# Iridium_9603_Beacon.net
KiCad netlist of a schematic drawn in EAGLE
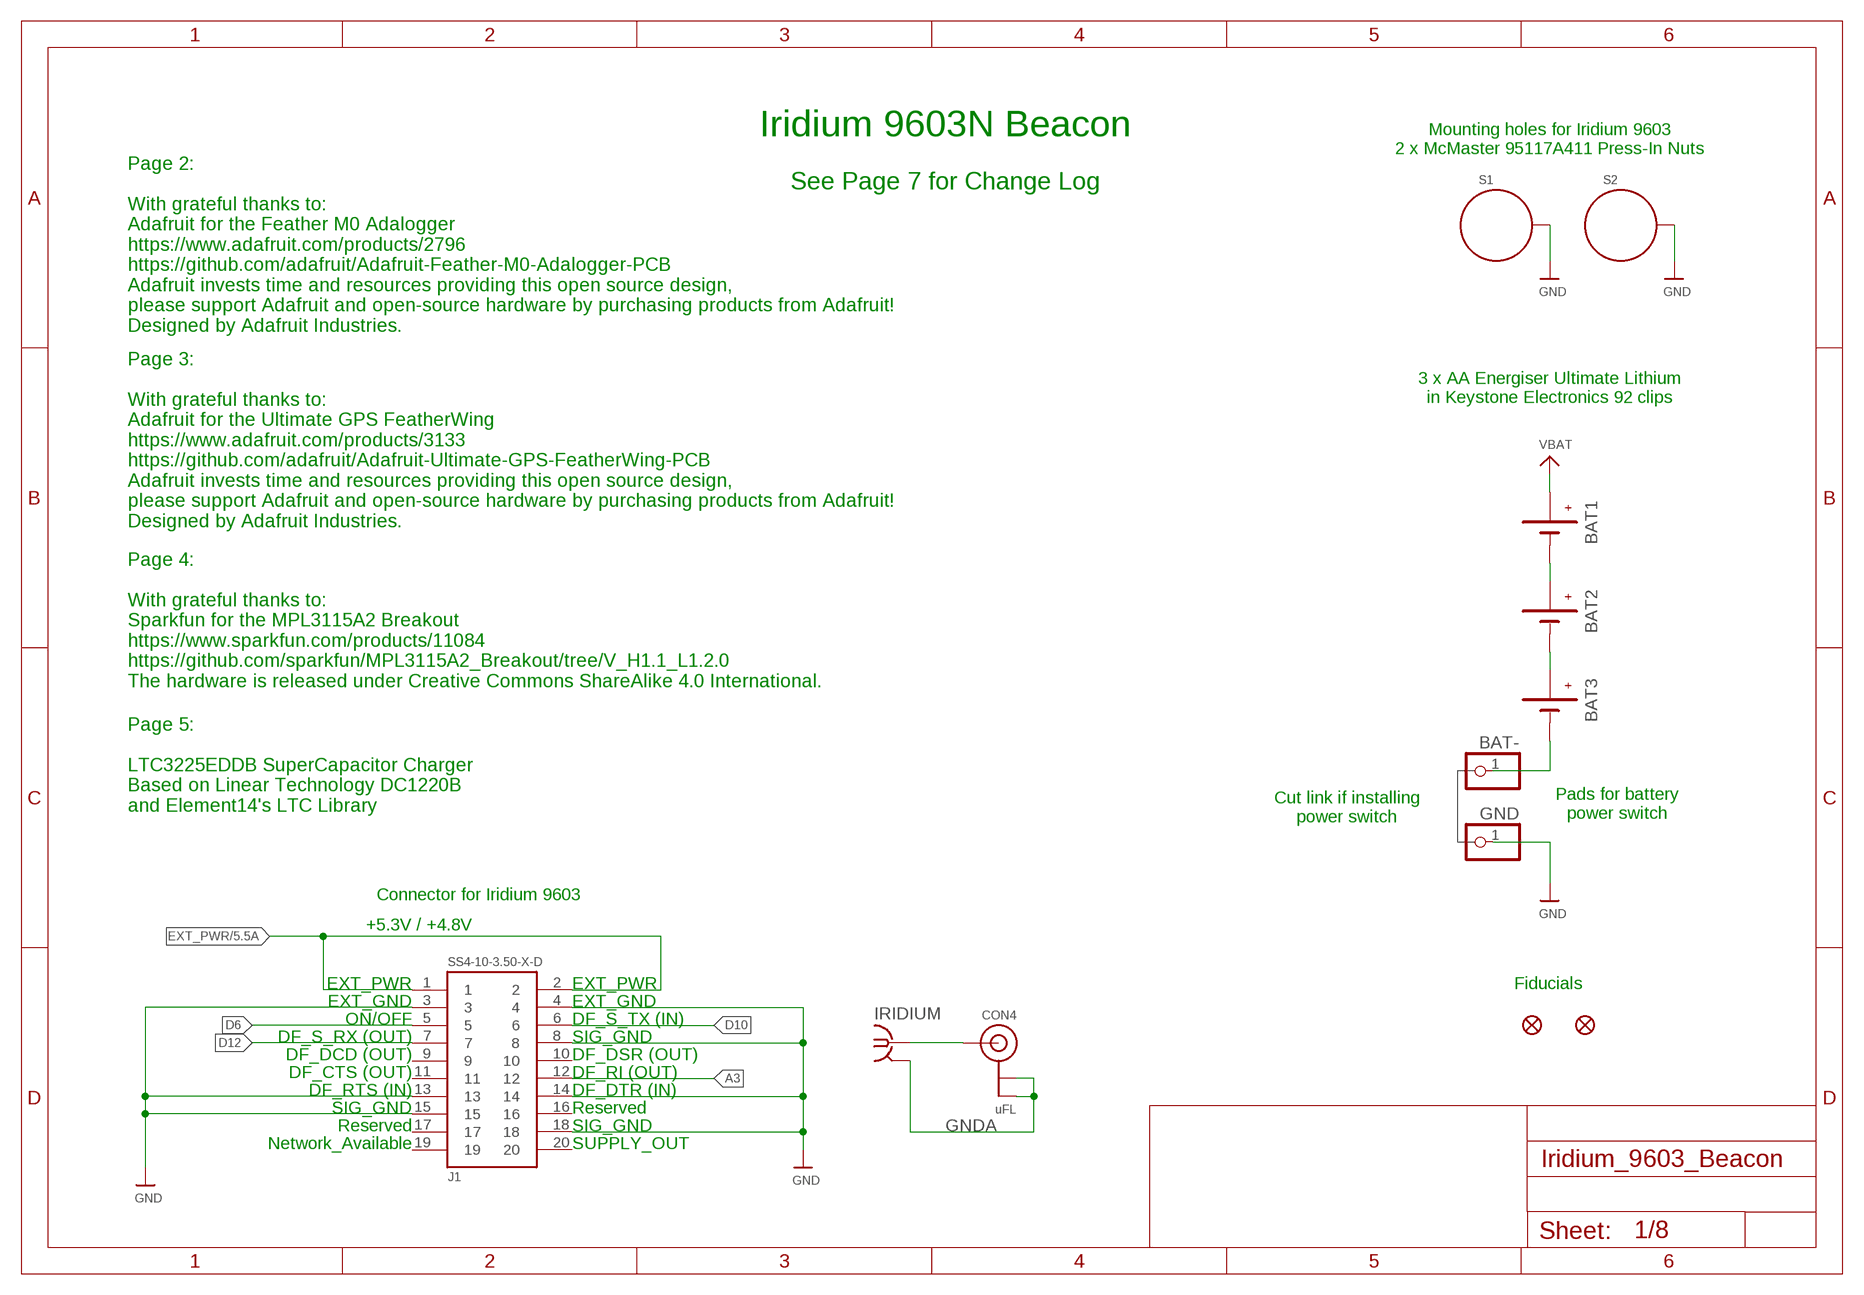
[diagram p0: schematic, sheet 1]
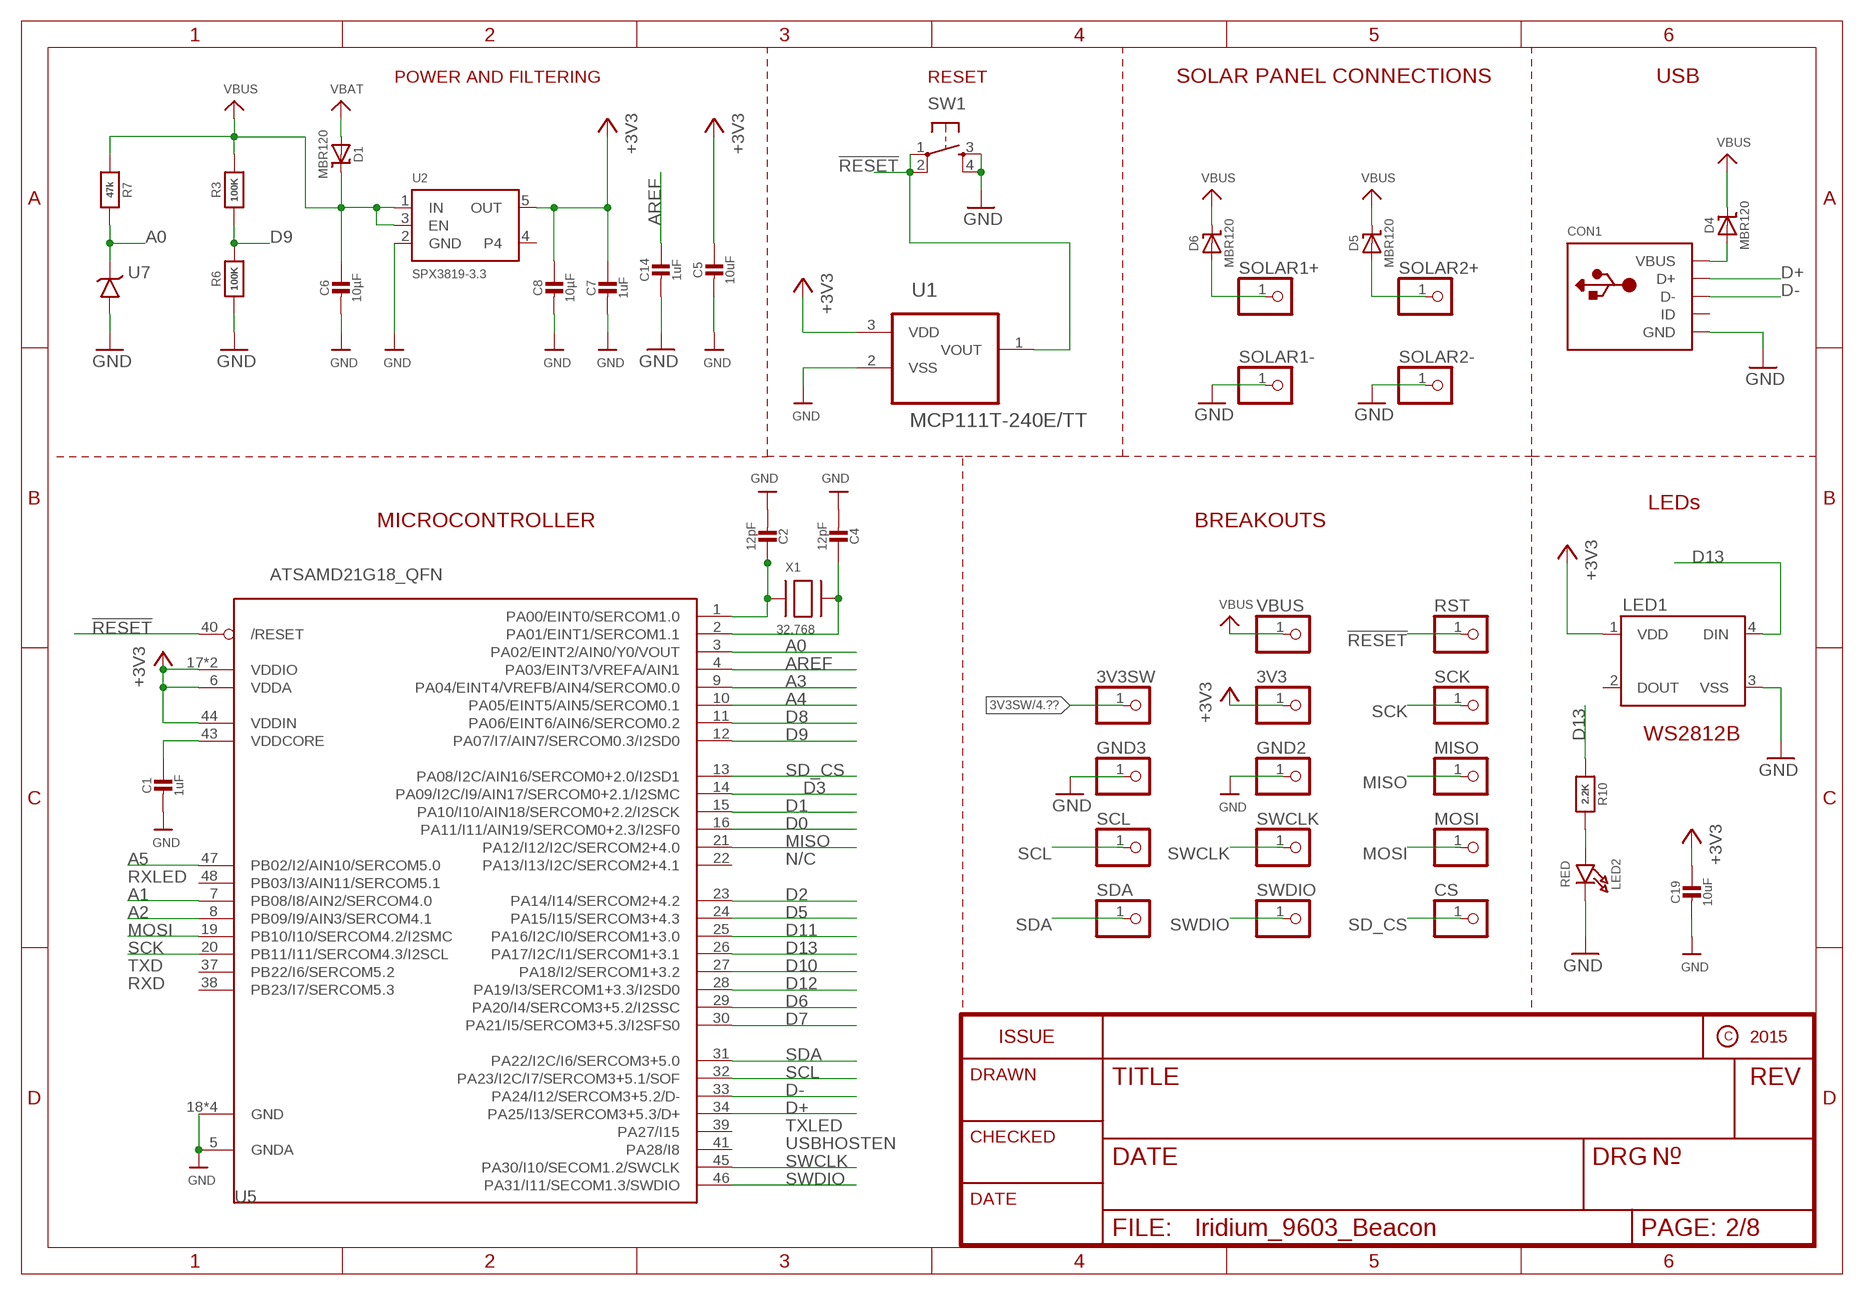
[diagram p1: schematic, sheet 2]
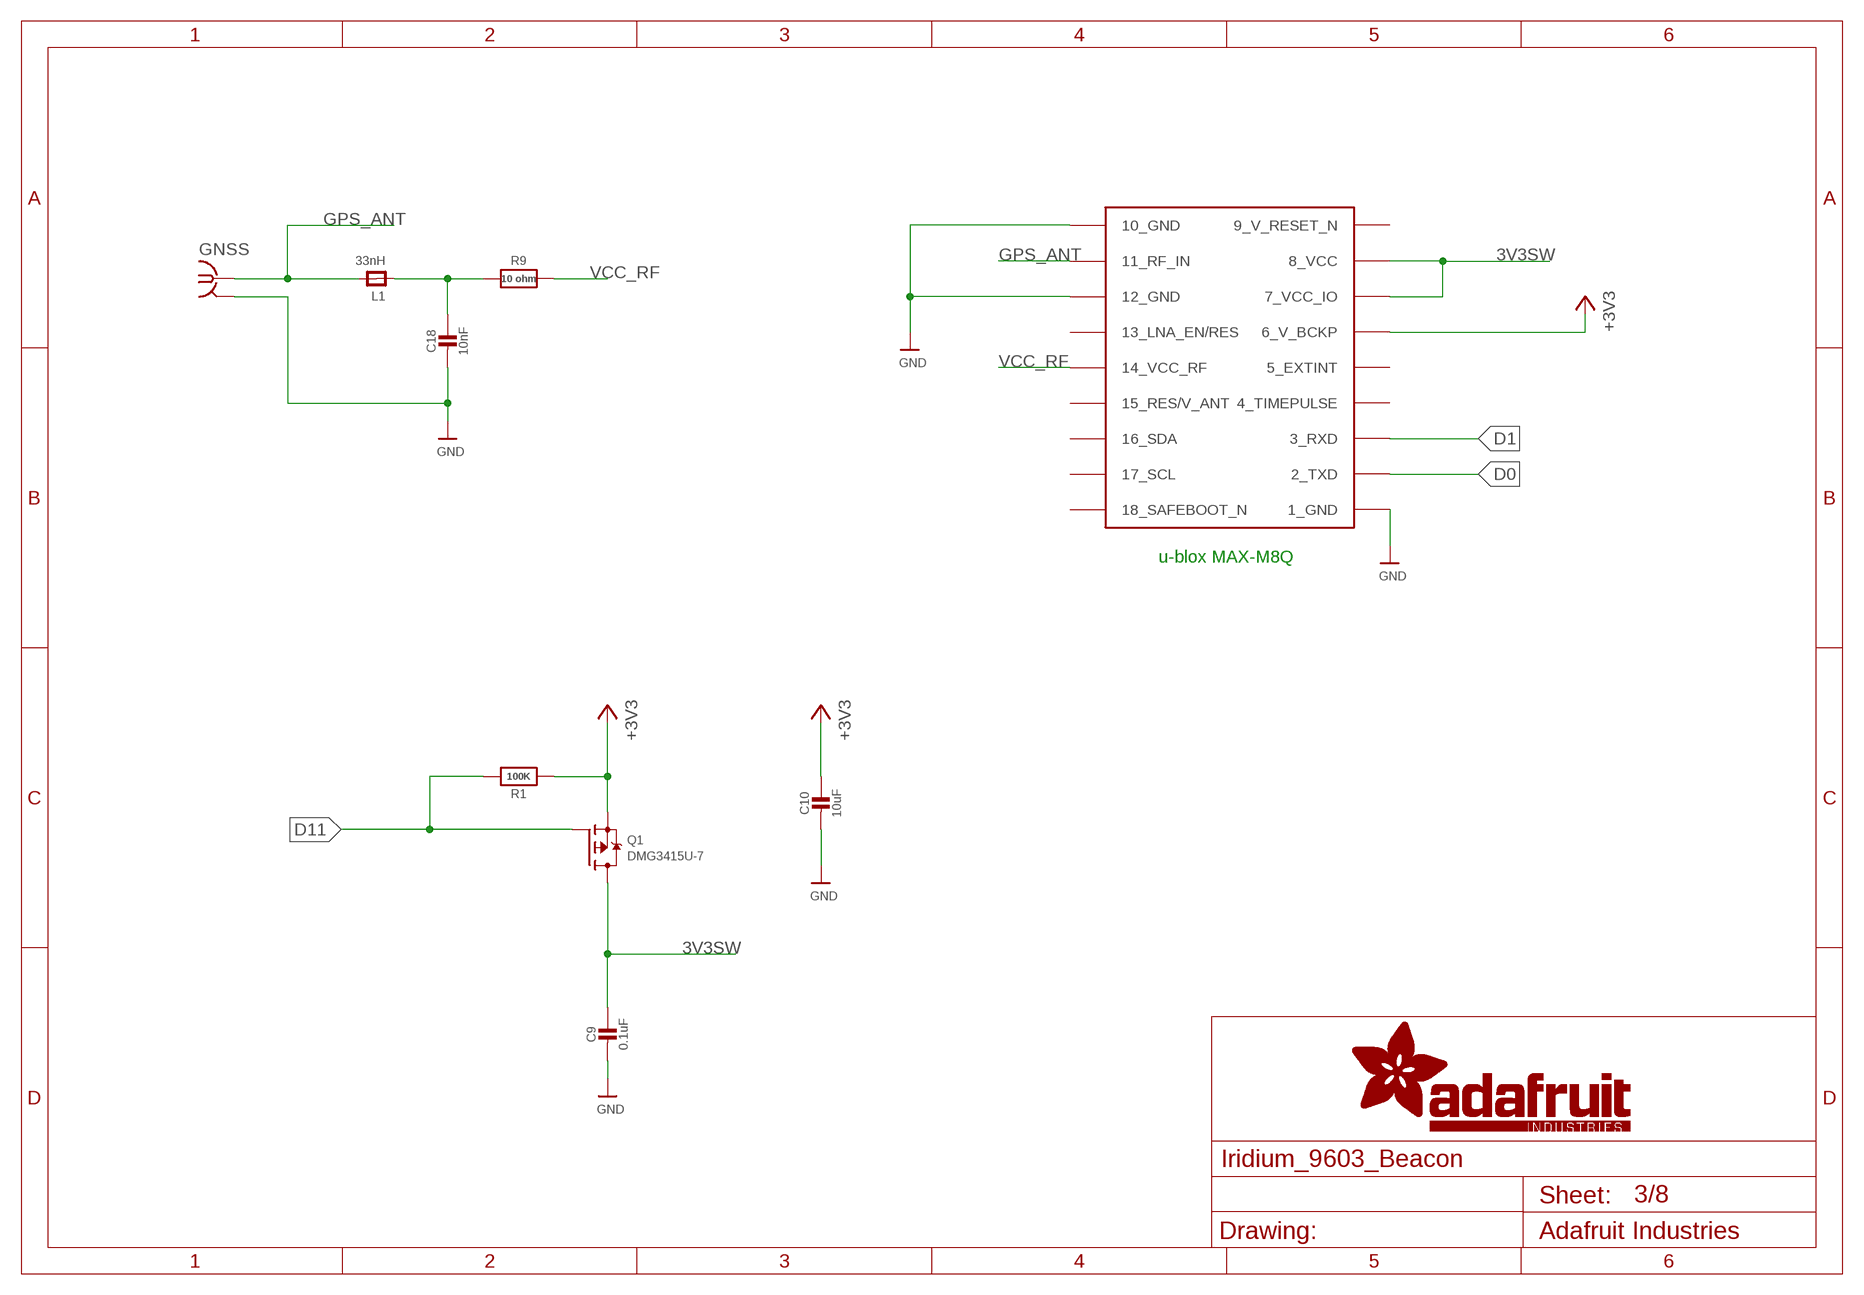
[diagram p2: schematic, sheet 3]
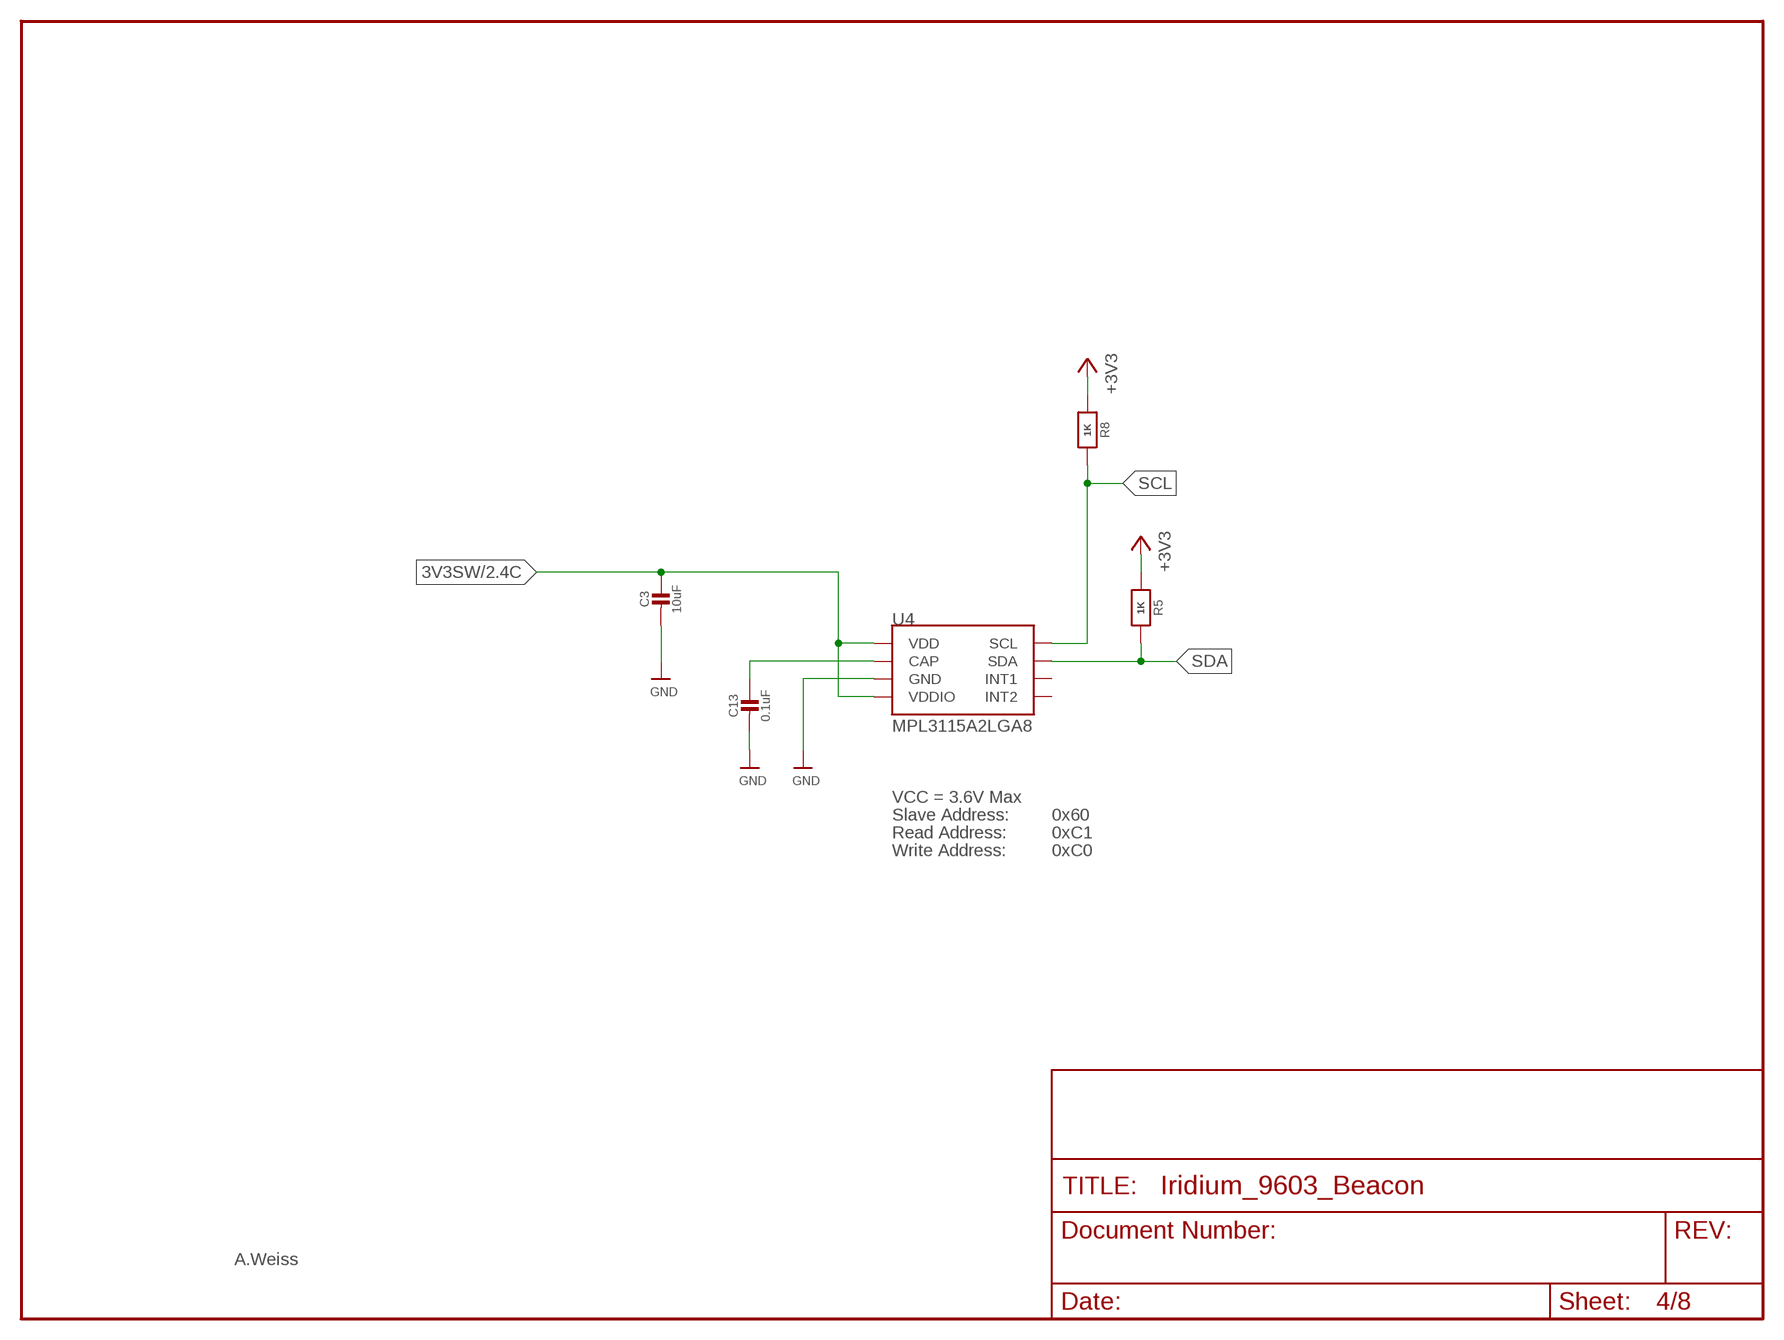
[diagram p3: schematic, sheet 4]
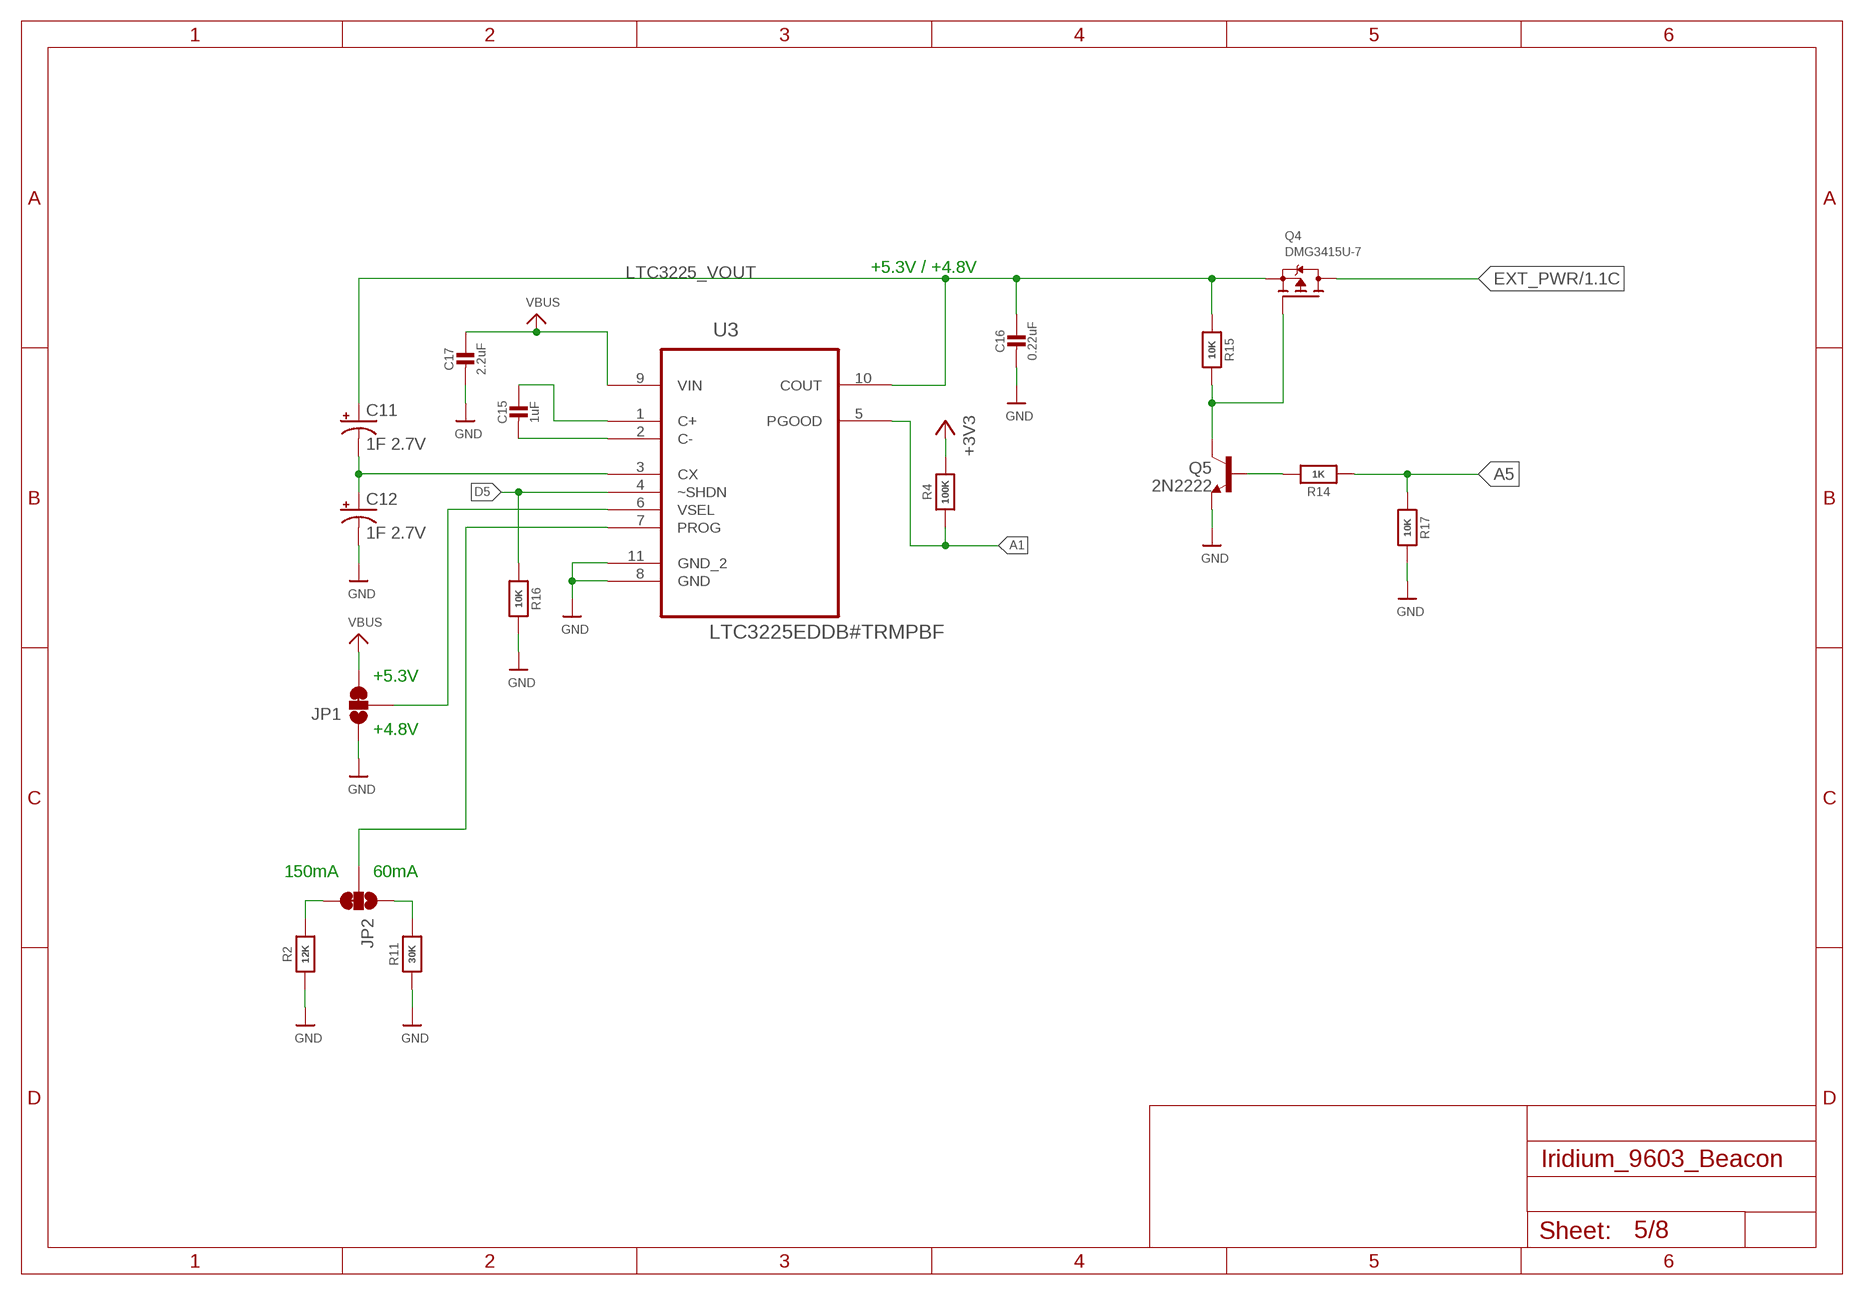
[diagram p4: schematic, sheet 5]
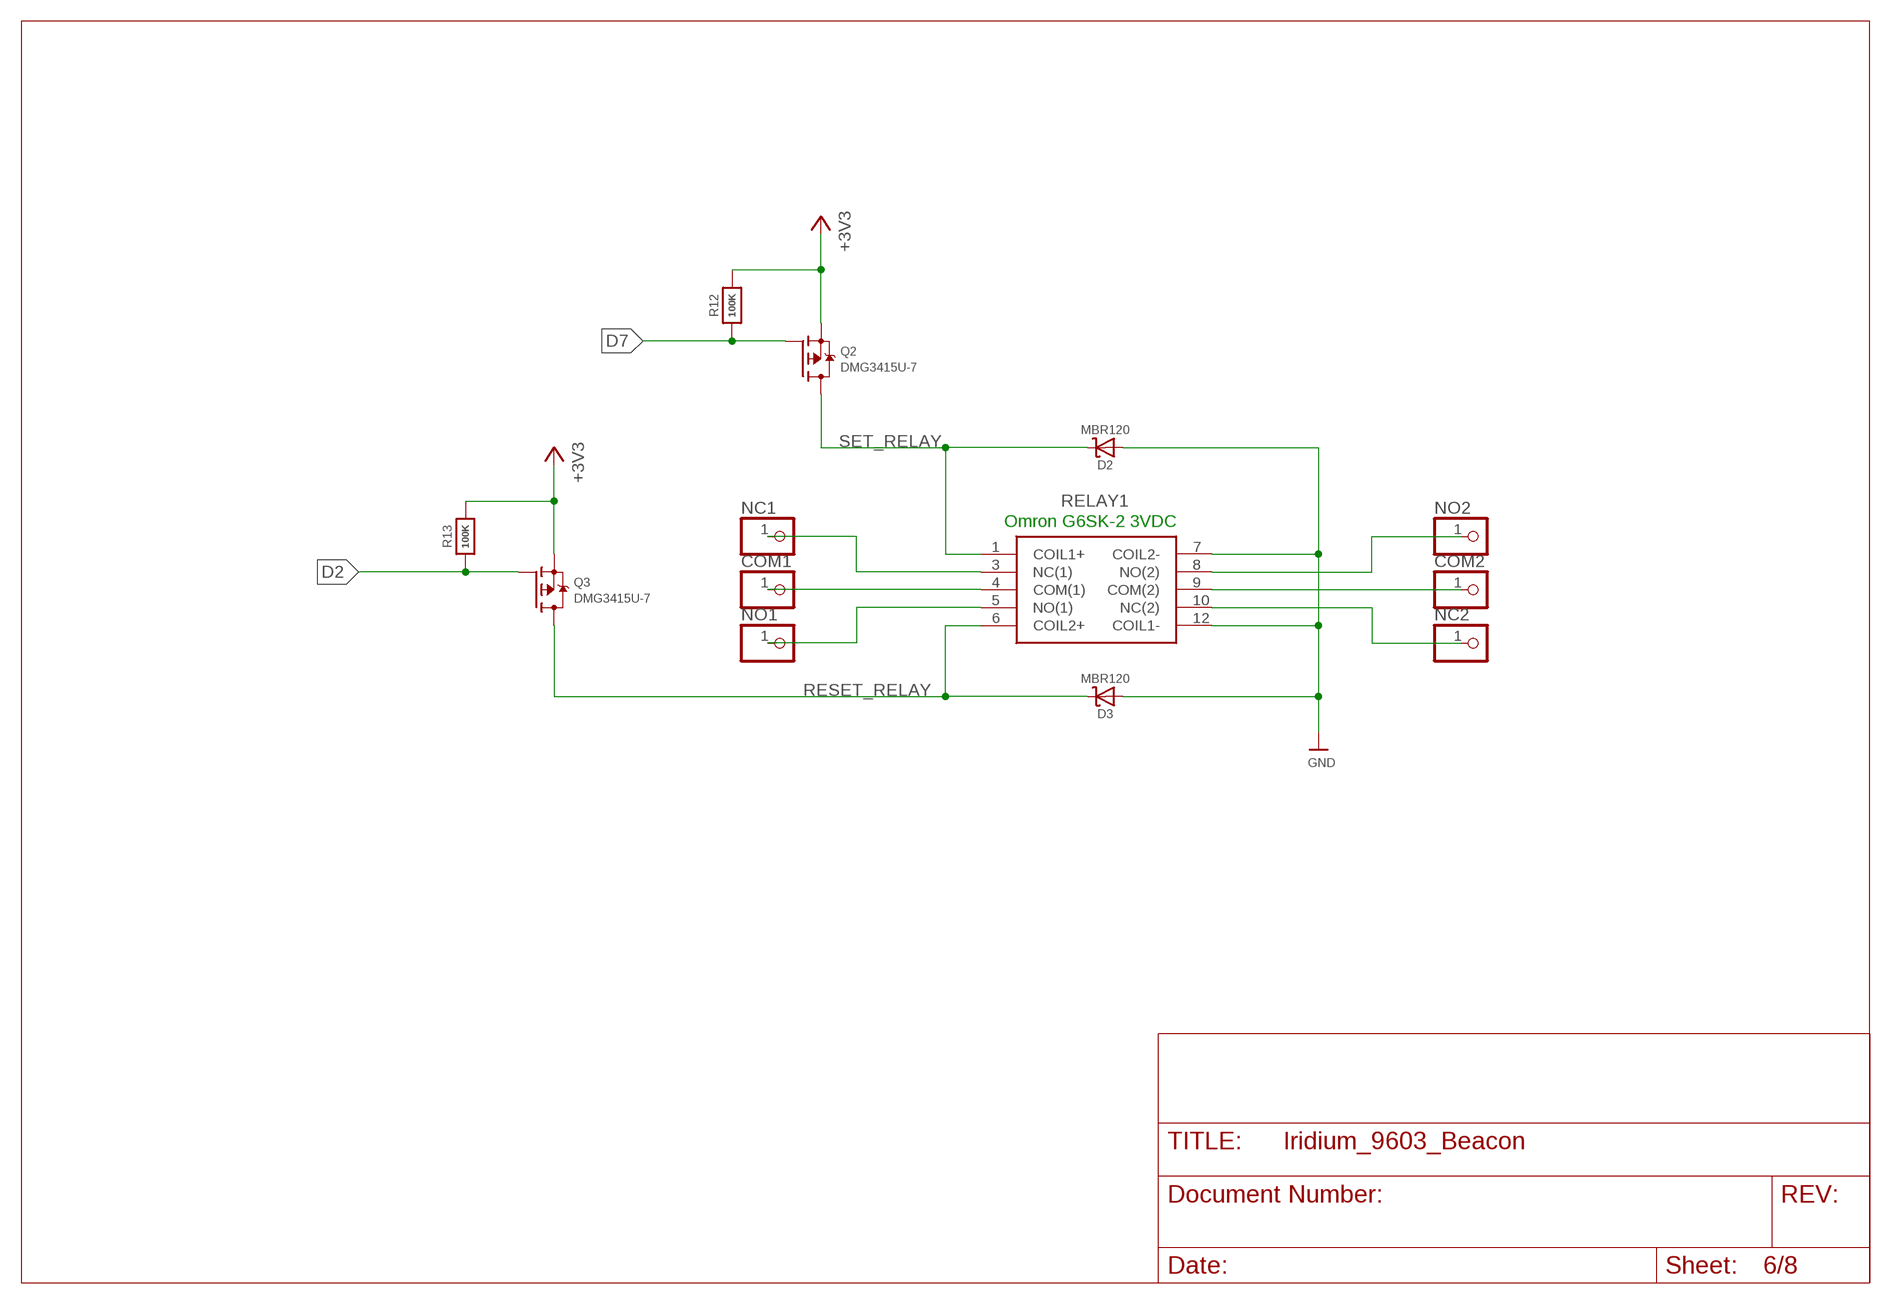
[diagram p5: schematic, sheet 6]
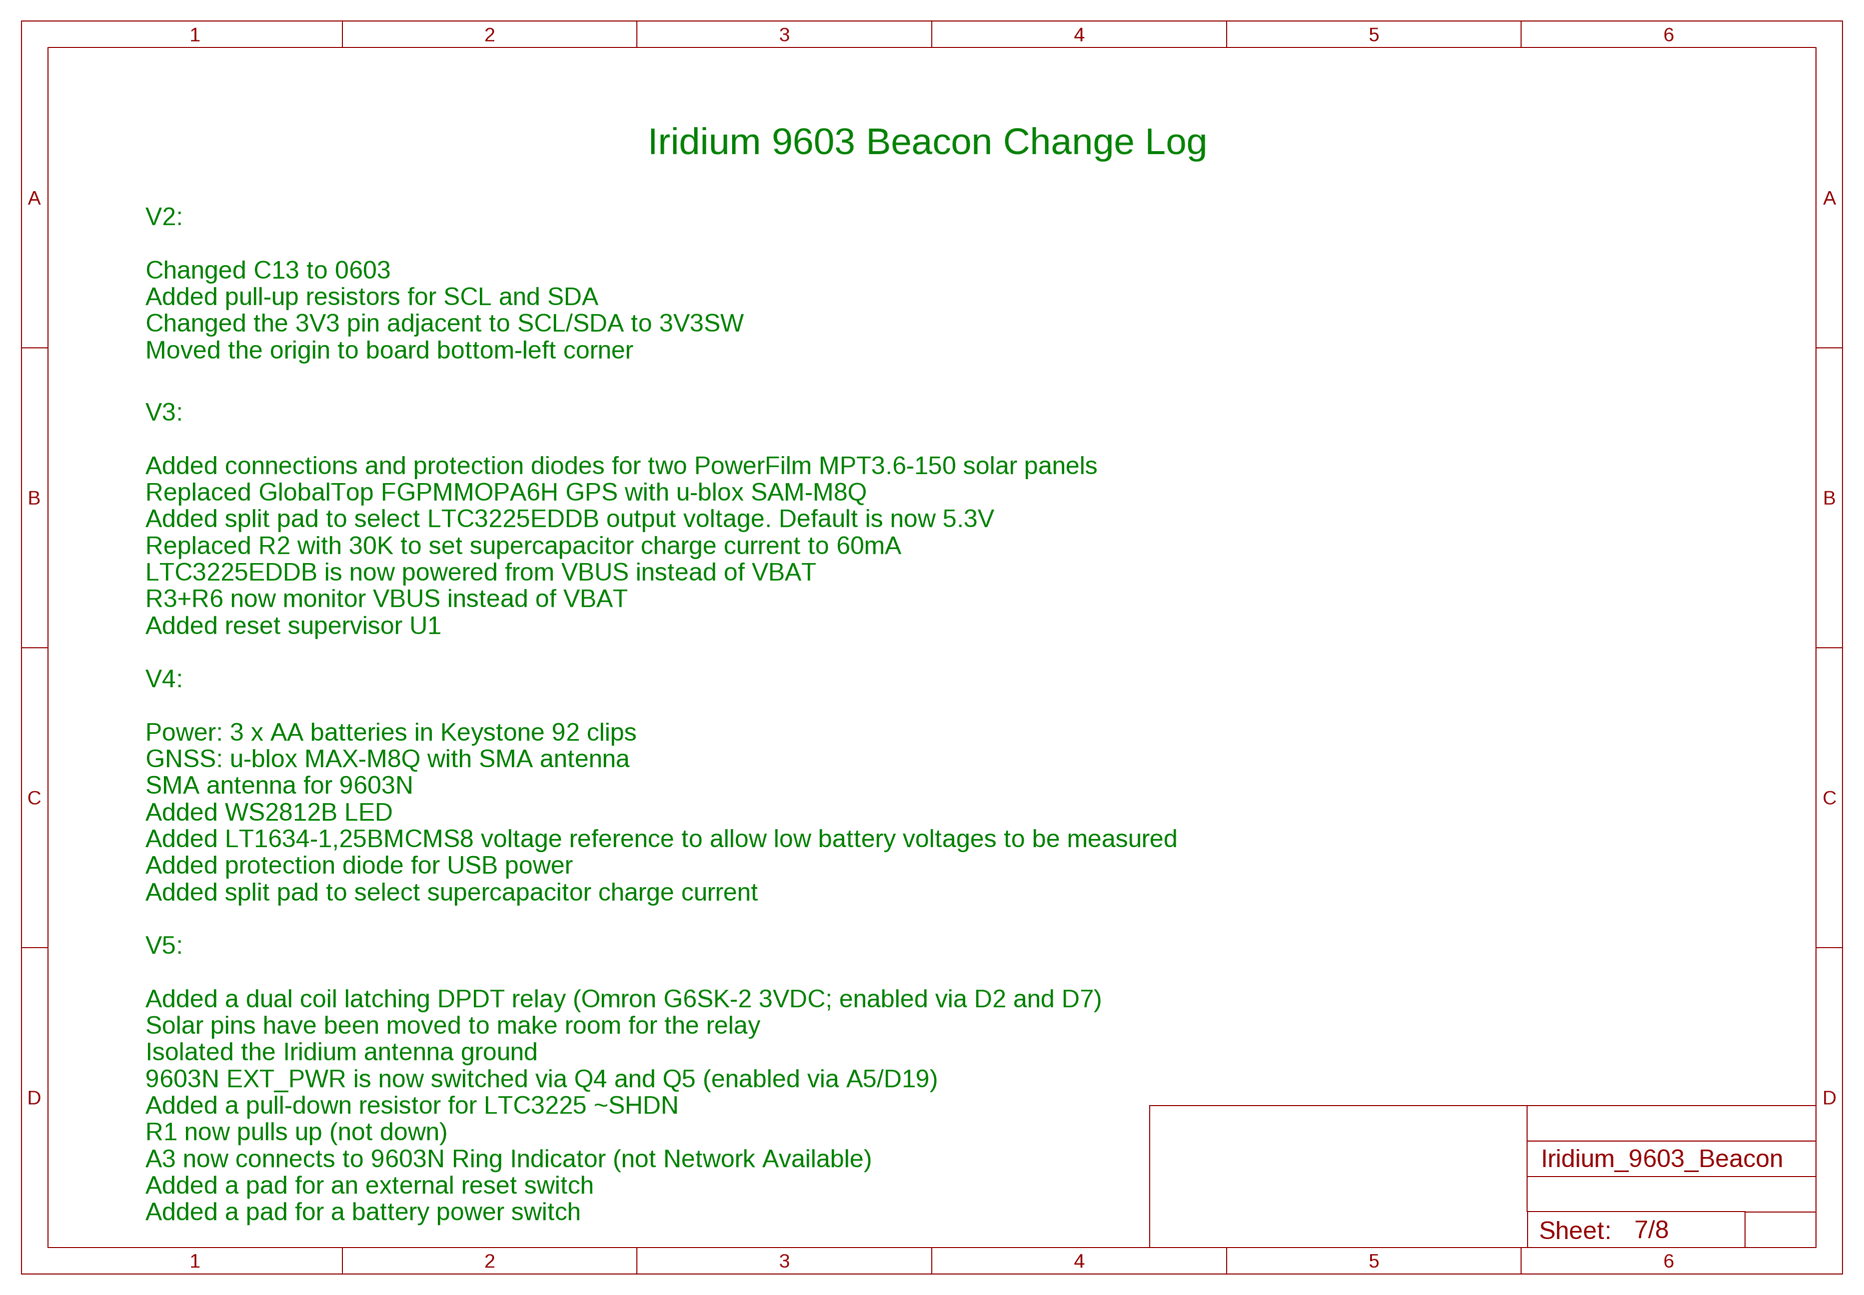
[diagram p6: schematic, sheet 7]
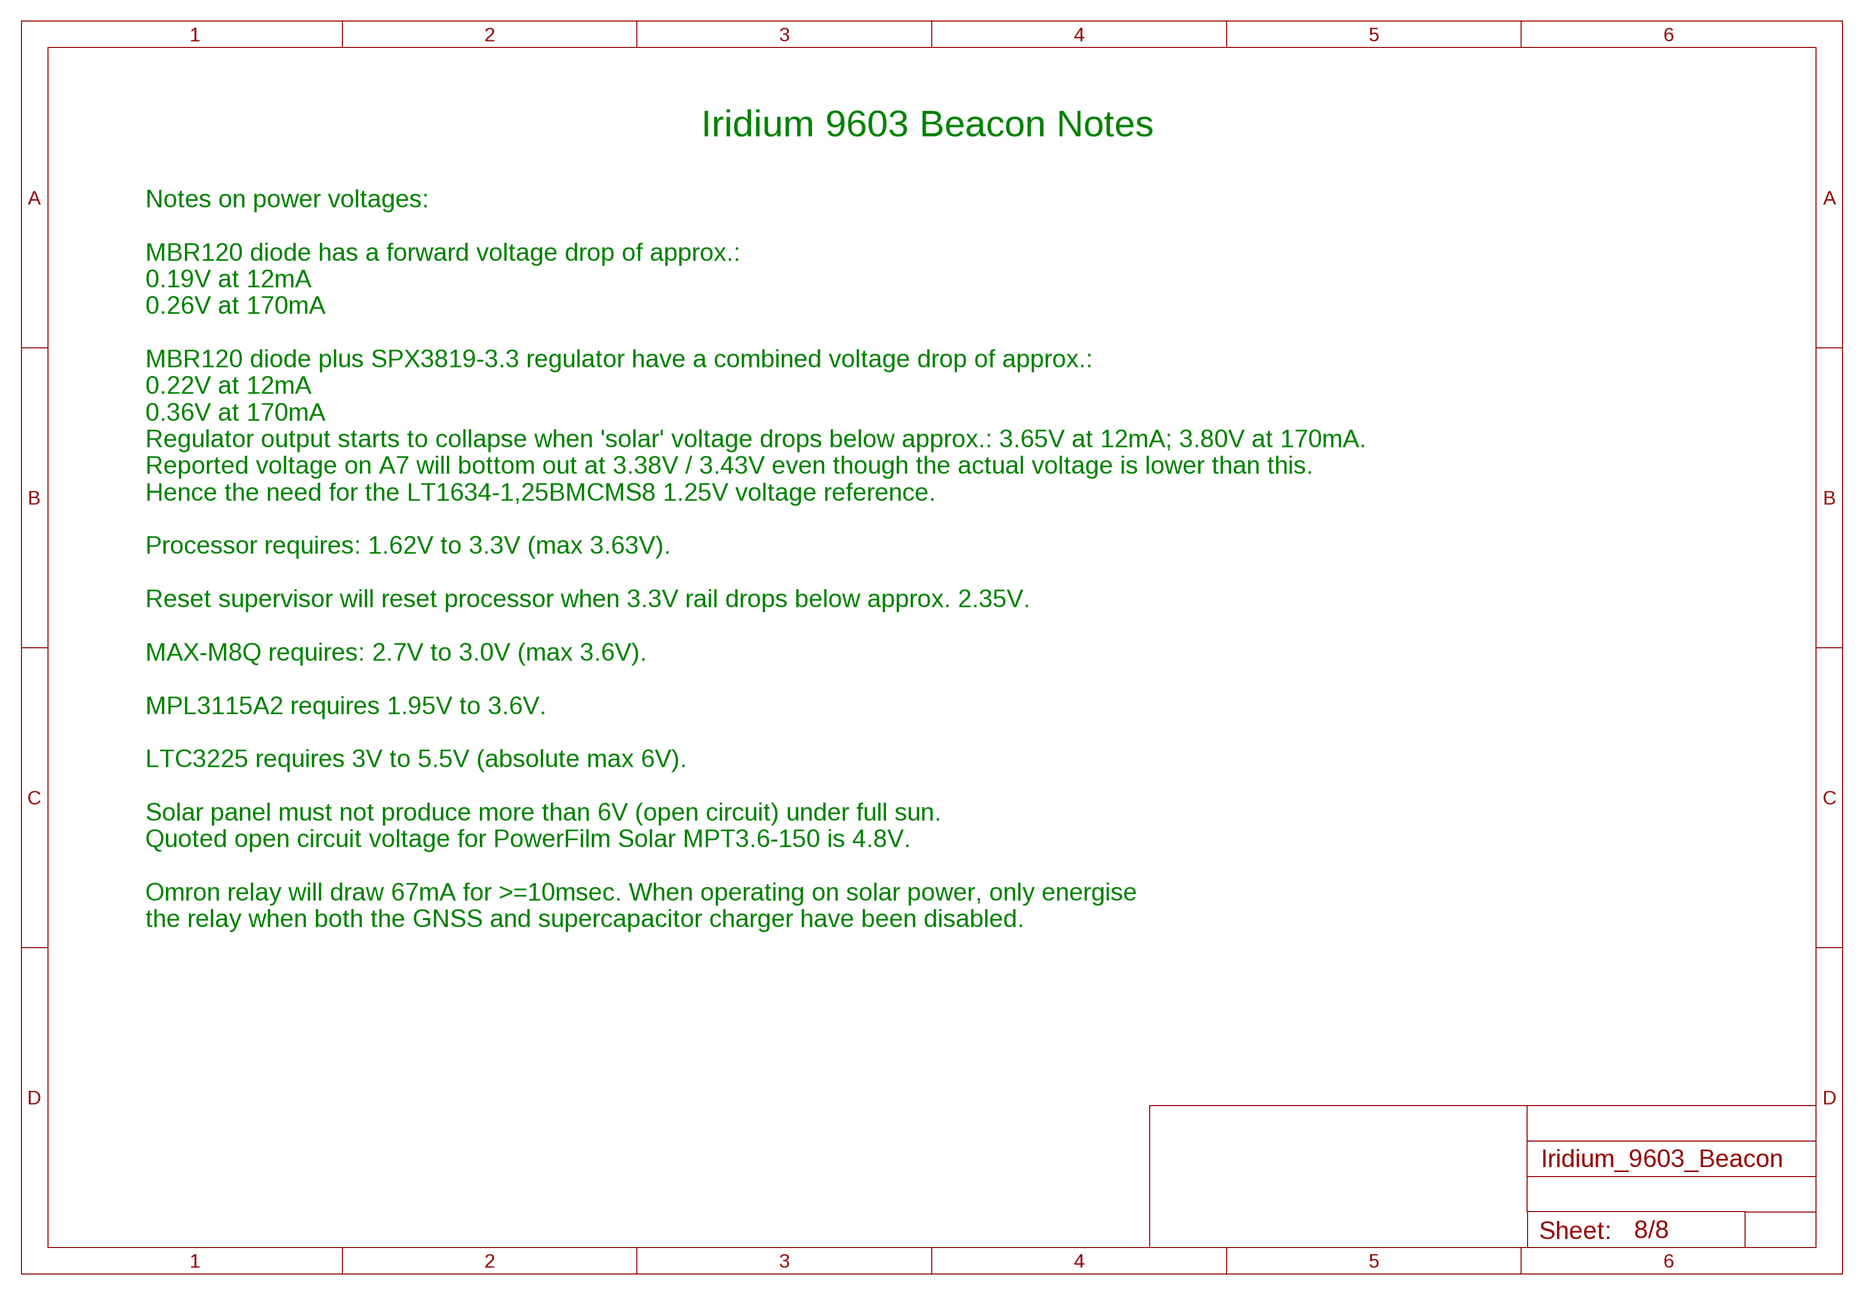
[diagram p7: schematic, sheet 8]

(export (version "E")
  (design (tool "Eeschema 10.0.6"))
  (components
    (comp (ref "C11")
      (value "1F 2.7V")
      (footprint "eagle-import:CPOL-RADIAL-1F-2.7V")
      (libsource (lib "eagle-import") (part "1F-2.7V(PTH)CPOL-RADIAL-1H-2.7V"))
    )
    (comp (ref "C12")
      (value "1F 2.7V")
      (footprint "eagle-import:CPOL-RADIAL-1F-2.7V")
      (libsource (lib "eagle-import") (part "1F-2.7V(PTH)CPOL-RADIAL-1H-2.7V"))
    )
    (comp (ref "C15")
      (value "1uF")
      (footprint "eagle-import:0603-NO")
      (libsource (lib "eagle-import") (part "CAP_CERAMIC0603_NO"))
    )
    (comp (ref "C16")
      (value "0.22uF")
      (footprint "eagle-import:0603-NO")
      (libsource (lib "eagle-import") (part "CAP_CERAMIC0603_NO"))
    )
    (comp (ref "C17")
      (value "2.2uF")
      (footprint "eagle-import:0805-NO")
      (libsource (lib "eagle-import") (part "CAP_CERAMIC0805-NOOUTLINE"))
    )
    (comp (ref "JP1")
      (value "JUMPER-PAD-3-2OF3_NC_BY_TRACE_LARGE")
      (footprint "eagle-import:PAD-JUMPER-3-2OF3_NC_BY_TRACE_YES_SILK_LARGE")
      (libsource (lib "eagle-import") (part "JUMPER-PAD-3-2OF3_NC_BY_TRACE_LARGE"))
    )
    (comp (ref "JP2")
      (value "JUMPER-PAD-3-2OF3_NC_BY_TRACE_LARGE")
      (footprint "eagle-import:PAD-JUMPER-3-2OF3_NC_BY_TRACE_YES_SILK_LARGE")
      (libsource (lib "eagle-import") (part "JUMPER-PAD-3-2OF3_NC_BY_TRACE_LARGE"))
    )
    (comp (ref "Q4")
      (value "DMG3415U-7")
      (footprint "eagle-import:SOT23-WIDE")
      (libsource (lib "eagle-import") (part "MOSFET-PWIDE"))
    )
    (comp (ref "Q5")
      (value "2N2222")
      (footprint "eagle-import:SOT23-BEC")
      (libsource (lib "eagle-import") (part "-NPN-SOT23-BECMMBT2222ALT1"))
    )
    (comp (ref "R2")
      (value "12K")
      (footprint "eagle-import:0805-NO")
      (libsource (lib "eagle-import") (part "RESISTOR0805_NOOUTLINE"))
    )
    (comp (ref "R4")
      (value "100K")
      (footprint "eagle-import:0805-NO")
      (libsource (lib "eagle-import") (part "RESISTOR0805_NOOUTLINE"))
    )
    (comp (ref "R11")
      (value "30K")
      (footprint "eagle-import:0805-NO")
      (libsource (lib "eagle-import") (part "RESISTOR0805_NOOUTLINE"))
    )
    (comp (ref "R14")
      (value "1K")
      (footprint "eagle-import:0603-NO")
      (libsource (lib "eagle-import") (part "RESISTOR_0603_NOOUT"))
    )
    (comp (ref "R15")
      (value "10K")
      (footprint "eagle-import:0603-NO")
      (libsource (lib "eagle-import") (part "RESISTOR_0603_NOOUT"))
    )
    (comp (ref "R16")
      (value "10K")
      (footprint "eagle-import:0603-NO")
      (libsource (lib "eagle-import") (part "RESISTOR_0603_NOOUT"))
    )
    (comp (ref "R17")
      (value "10K")
      (footprint "eagle-import:0603-NO")
      (libsource (lib "eagle-import") (part "RESISTOR_0603_NOOUT"))
    )
    (comp (ref "U3")
      (value "LTC3225EDDB#TRMPBF")
      (footprint "eagle-import:DFN300X200-10L")
      (libsource (lib "eagle-import") (part "LTC3225EDDB-TRMPBFDFN300X200-10L"))
    )
    (comp (ref "BAT-")
      (value "PINHD-1X1")
      (footprint "eagle-import:1X01")
      (libsource (lib "eagle-import") (part "PINHD-1X1"))
    )
    (comp (ref "BAT1")
      (value "BATTERYKEYSTONE92")
      (footprint "eagle-import:BATTERY-AAA-KEYSTONE92")
      (libsource (lib "eagle-import") (part "BATTERYKEYSTONE92"))
    )
    (comp (ref "BAT2")
      (value "BATTERYKEYSTONE92")
      (footprint "eagle-import:BATTERY-AAA-KEYSTONE92")
      (libsource (lib "eagle-import") (part "BATTERYKEYSTONE92"))
    )
    (comp (ref "BAT3")
      (value "BATTERYKEYSTONE92")
      (footprint "eagle-import:BATTERY-AAA-KEYSTONE92")
      (libsource (lib "eagle-import") (part "BATTERYKEYSTONE92"))
    )
    (comp (ref "CON4")
      (value "uFL")
      (footprint "eagle-import:U.FL")
      (libsource (lib "eagle-import") (part "ANTENNA_U.FL"))
    )
    (comp (ref "FD1")
      (value "FIDUCIAL1X2")
      (footprint "eagle-import:FIDUCIAL-1X2")
      (libsource (lib "eagle-import") (part "FIDUCIAL1X2"))
    )
    (comp (ref "FD2")
      (value "FIDUCIAL1X2")
      (footprint "eagle-import:FIDUCIAL-1X2")
      (libsource (lib "eagle-import") (part "FIDUCIAL1X2"))
    )
    (comp (ref "GND")
      (value "PINHD-1X1")
      (footprint "eagle-import:1X01")
      (libsource (lib "eagle-import") (part "PINHD-1X1"))
    )
    (comp (ref "IRIDIUM")
      (value "SMA-142-0711-821/826")
      (footprint "eagle-import:J502-ND-142-0711-821_826")
      (fields (field (name "MF") "JOHNSON COMPONENTS") (field (name "MPN") "142-0711-821"))
      (libsource (lib "eagle-import") (part "con-coax_133_SMA-142-0711-821/826"))
    )
    (comp (ref "J1")
      (value "SS4-10-3.50-X-D")
      (footprint "eagle-import:SS4-10-3.50-X-D")
      (libsource (lib "eagle-import") (part "SS4-10-3.50-X-D"))
    )
    (comp (ref "S1")
      (value "STANDOFF_ELECTRICALMCMASTER-95117A411")
      (footprint "eagle-import:STANDOFF-ELECTRICAL-MCMASTER-95117A411")
      (libsource (lib "eagle-import") (part "STANDOFF_ELECTRICALMCMASTER-95117A411"))
    )
    (comp (ref "S2")
      (value "STANDOFF_ELECTRICALMCMASTER-95117A411")
      (footprint "eagle-import:STANDOFF-ELECTRICAL-MCMASTER-95117A411")
      (libsource (lib "eagle-import") (part "STANDOFF_ELECTRICALMCMASTER-95117A411"))
    )
    (comp (ref "C3")
      (value "10uF")
      (footprint "eagle-import:0805-NO")
      (libsource (lib "eagle-import") (part "CAP_CERAMIC0805-NOOUTLINE"))
    )
    (comp (ref "C13")
      (value "0.1uF")
      (footprint "eagle-import:0805-NO")
      (libsource (lib "eagle-import") (part "CAP_CERAMIC0805-NOOUTLINE"))
    )
    (comp (ref "R5")
      (value "1K")
      (footprint "eagle-import:0603-NO")
      (libsource (lib "eagle-import") (part "RESISTOR_0603_NOOUT"))
    )
    (comp (ref "R8")
      (value "1K")
      (footprint "eagle-import:0603-NO")
      (libsource (lib "eagle-import") (part "RESISTOR_0603_NOOUT"))
    )
    (comp (ref "U4")
      (value "MPL3115A2LGA8")
      (footprint "eagle-import:LGA8")
      (libsource (lib "eagle-import") (part "MPL3115A2LGA8"))
    )
    (comp (ref "COM1")
      (value "PINHD-1X1")
      (footprint "eagle-import:1X01")
      (libsource (lib "eagle-import") (part "PINHD-1X1"))
    )
    (comp (ref "COM2")
      (value "PINHD-1X1")
      (footprint "eagle-import:1X01")
      (libsource (lib "eagle-import") (part "PINHD-1X1"))
    )
    (comp (ref "D2")
      (value "MBR120")
      (footprint "eagle-import:SOD-123")
      (libsource (lib "eagle-import") (part "DIODE-SCHOTTKYSOD-123"))
    )
    (comp (ref "D3")
      (value "MBR120")
      (footprint "eagle-import:SOD-123")
      (libsource (lib "eagle-import") (part "DIODE-SCHOTTKYSOD-123"))
    )
    (comp (ref "NC1")
      (value "PINHD-1X1")
      (footprint "eagle-import:1X01")
      (libsource (lib "eagle-import") (part "PINHD-1X1"))
    )
    (comp (ref "NC2")
      (value "PINHD-1X1")
      (footprint "eagle-import:1X01")
      (libsource (lib "eagle-import") (part "PINHD-1X1"))
    )
    (comp (ref "NO1")
      (value "PINHD-1X1")
      (footprint "eagle-import:1X01")
      (libsource (lib "eagle-import") (part "PINHD-1X1"))
    )
    (comp (ref "NO2")
      (value "PINHD-1X1")
      (footprint "eagle-import:1X01")
      (libsource (lib "eagle-import") (part "PINHD-1X1"))
    )
    (comp (ref "Q2")
      (value "DMG3415U-7")
      (footprint "eagle-import:SOT23-WIDE")
      (libsource (lib "eagle-import") (part "MOSFET-PWIDE"))
    )
    (comp (ref "Q3")
      (value "DMG3415U-7")
      (footprint "eagle-import:SOT23-WIDE")
      (libsource (lib "eagle-import") (part "MOSFET-PWIDE"))
    )
    (comp (ref "R12")
      (value "100K")
      (footprint "eagle-import:0805-NO")
      (libsource (lib "eagle-import") (part "RESISTOR0805_NOOUTLINE"))
    )
    (comp (ref "R13")
      (value "100K")
      (footprint "eagle-import:0805-NO")
      (libsource (lib "eagle-import") (part "RESISTOR0805_NOOUTLINE"))
    )
    (comp (ref "RELAY1")
      (value "G6SK-2_DC5")
      (footprint "eagle-import:G6SK2DC5")
      (fields (field (name "MANUFACTURER_PART_NUMBER") "G6SK-2 DC5"))
      (libsource (lib "eagle-import") (part "G6SK-2_DC5"))
    )
    (comp (ref "C9")
      (value "0.1uF")
      (footprint "eagle-import:0805-NO")
      (libsource (lib "eagle-import") (part "CAP_CERAMIC0805-NOOUTLINE"))
    )
    (comp (ref "C10")
      (value "10uF")
      (footprint "eagle-import:0805-NO")
      (libsource (lib "eagle-import") (part "CAP_CERAMIC0805-NOOUTLINE"))
    )
    (comp (ref "C18")
      (value "10nF")
      (footprint "eagle-import:0805-NO")
      (libsource (lib "eagle-import") (part "CAP_CERAMIC0805-NOOUTLINE"))
    )
    (comp (ref "GNSS")
      (value "SMA-142-0711-821/826")
      (footprint "eagle-import:J502-ND-142-0711-821_826")
      (fields (field (name "MF") "JOHNSON COMPONENTS") (field (name "MPN") "142-0711-821"))
      (libsource (lib "eagle-import") (part "SMA-142-0711-821/826"))
    )
    (comp (ref "L1")
      (value "33nH")
      (footprint "eagle-import:0805-NO")
      (libsource (lib "eagle-import") (part "FERRITE-0805NO"))
    )
    (comp (ref "Q1")
      (value "DMG3415U-7")
      (footprint "eagle-import:SOT23-WIDE")
      (libsource (lib "eagle-import") (part "MOSFET-PWIDE"))
    )
    (comp (ref "R1")
      (value "100K")
      (footprint "eagle-import:0805-NO")
      (libsource (lib "eagle-import") (part "RESISTOR0805_NOOUTLINE"))
    )
    (comp (ref "R9")
      (value "10 ohm")
      (footprint "eagle-import:0805-NO")
      (libsource (lib "eagle-import") (part "RESISTOR0805_NOOUTLINE"))
    )
    (comp (ref "U6")
      (value "MAX-M8")
      (footprint "eagle-import:MAX-M8")
      (libsource (lib "eagle-import") (part "MAX-M8"))
    )
    (comp (ref "3V3")
      (value "PINHD-1X1")
      (footprint "eagle-import:1X01")
      (libsource (lib "eagle-import") (part "PINHD-1X1"))
    )
    (comp (ref "3V3SW")
      (value "PINHD-1X1")
      (footprint "eagle-import:1X01")
      (libsource (lib "eagle-import") (part "PINHD-1X1"))
    )
    (comp (ref "C1")
      (value "1uF")
      (footprint "eagle-import:0603-NO")
      (libsource (lib "eagle-import") (part "CAP_CERAMIC0603_NO"))
    )
    (comp (ref "C2")
      (value "12pF")
      (footprint "eagle-import:0603-NO")
      (libsource (lib "eagle-import") (part "CAP_CERAMIC0603_NO"))
    )
    (comp (ref "C4")
      (value "12pF")
      (footprint "eagle-import:0603-NO")
      (libsource (lib "eagle-import") (part "CAP_CERAMIC0603_NO"))
    )
    (comp (ref "C5")
      (value "10uF")
      (footprint "eagle-import:0805-NO")
      (libsource (lib "eagle-import") (part "CAP_CERAMIC0805-NOOUTLINE"))
    )
    (comp (ref "C6")
      (value "10µF")
      (footprint "eagle-import:0805-NO")
      (libsource (lib "eagle-import") (part "CAP_CERAMIC0805-NOOUTLINE"))
    )
    (comp (ref "C7")
      (value "1uF")
      (footprint "eagle-import:0603-NO")
      (libsource (lib "eagle-import") (part "CAP_CERAMIC0603_NO"))
    )
    (comp (ref "C8")
      (value "10µF")
      (footprint "eagle-import:0805-NO")
      (libsource (lib "eagle-import") (part "CAP_CERAMIC0805-NOOUTLINE"))
    )
    (comp (ref "C14")
      (value "1uF")
      (footprint "eagle-import:0603-NO")
      (libsource (lib "eagle-import") (part "CAP_CERAMIC0603_NO"))
    )
    (comp (ref "C19")
      (value "10uF")
      (footprint "eagle-import:0805-NO")
      (libsource (lib "eagle-import") (part "CAP_CERAMIC0805-NOOUTLINE"))
    )
    (comp (ref "CON1")
      (value "MICROBUILDER_USBFCI_10103594_CORRECTED")
      (footprint "eagle-import:MICROBUILDER_FCI_10103594_CORRECTED")
      (libsource (lib "eagle-import") (part "MICROBUILDER_USBFCI_10103594_CORRECTED"))
    )
    (comp (ref "CS")
      (value "PINHD-1X1")
      (footprint "eagle-import:1X01")
      (libsource (lib "eagle-import") (part "PINHD-1X1"))
    )
    (comp (ref "D1")
      (value "MBR120")
      (footprint "eagle-import:SOD-123")
      (libsource (lib "eagle-import") (part "DIODE-SCHOTTKYSOD-123"))
    )
    (comp (ref "D4")
      (value "MBR120")
      (footprint "eagle-import:SOD-123")
      (libsource (lib "eagle-import") (part "DIODE-SCHOTTKYSOD-123"))
    )
    (comp (ref "D5")
      (value "MBR120")
      (footprint "eagle-import:SOD-123")
      (libsource (lib "eagle-import") (part "DIODE-SCHOTTKYSOD-123"))
    )
    (comp (ref "D6")
      (value "MBR120")
      (footprint "eagle-import:SOD-123")
      (libsource (lib "eagle-import") (part "DIODE-SCHOTTKYSOD-123"))
    )
    (comp (ref "GND2")
      (value "PINHD-1X1")
      (footprint "eagle-import:1X01")
      (libsource (lib "eagle-import") (part "PINHD-1X1"))
    )
    (comp (ref "GND3")
      (value "PINHD-1X1")
      (footprint "eagle-import:1X01")
      (libsource (lib "eagle-import") (part "PINHD-1X1"))
    )
    (comp (ref "LED1")
      (value "WS2812B")
      (footprint "eagle-import:WS2812B")
      (libsource (lib "eagle-import") (part "WS2812B"))
    )
    (comp (ref "LED2")
      (value "RED")
      (footprint "eagle-import:CHIPLED_0805_NOOUTLINE")
      (libsource (lib "eagle-import") (part "LED0805_NOOUTLINE"))
    )
    (comp (ref "MISO")
      (value "PINHD-1X1")
      (footprint "eagle-import:1X01")
      (libsource (lib "eagle-import") (part "PINHD-1X1"))
    )
    (comp (ref "MOSI")
      (value "PINHD-1X1")
      (footprint "eagle-import:1X01")
      (libsource (lib "eagle-import") (part "PINHD-1X1"))
    )
    (comp (ref "R3")
      (value "100K")
      (footprint "eagle-import:0805-NO")
      (libsource (lib "eagle-import") (part "RESISTOR0805_NOOUTLINE"))
    )
    (comp (ref "R6")
      (value "100K")
      (footprint "eagle-import:0805-NO")
      (libsource (lib "eagle-import") (part "RESISTOR0805_NOOUTLINE"))
    )
    (comp (ref "R7")
      (value "47k")
      (footprint "eagle-import:0603-NO")
      (libsource (lib "eagle-import") (part "RESISTOR_0603_NOOUT"))
    )
    (comp (ref "R10")
      (value "2.2K")
      (footprint "eagle-import:0603-NO")
      (libsource (lib "eagle-import") (part "RESISTOR_0603_NOOUT"))
    )
    (comp (ref "RST")
      (value "PINHD-1X1")
      (footprint "eagle-import:1X01")
      (libsource (lib "eagle-import") (part "PINHD-1X1"))
    )
    (comp (ref "SCK")
      (value "PINHD-1X1")
      (footprint "eagle-import:1X01")
      (libsource (lib "eagle-import") (part "PINHD-1X1"))
    )
    (comp (ref "SCL")
      (value "PINHD-1X1")
      (footprint "eagle-import:1X01")
      (libsource (lib "eagle-import") (part "PINHD-1X1"))
    )
    (comp (ref "SDA")
      (value "PINHD-1X1")
      (footprint "eagle-import:1X01")
      (libsource (lib "eagle-import") (part "PINHD-1X1"))
    )
    (comp (ref "SOLAR1+")
      (value "PINHD-1X1")
      (footprint "eagle-import:1X01")
      (libsource (lib "eagle-import") (part "PINHD-1X1"))
    )
    (comp (ref "SOLAR1-")
      (value "PINHD-1X1")
      (footprint "eagle-import:1X01")
      (libsource (lib "eagle-import") (part "PINHD-1X1"))
    )
    (comp (ref "SOLAR2+")
      (value "PINHD-1X1")
      (footprint "eagle-import:1X01")
      (libsource (lib "eagle-import") (part "PINHD-1X1"))
    )
    (comp (ref "SOLAR2-")
      (value "PINHD-1X1")
      (footprint "eagle-import:1X01")
      (libsource (lib "eagle-import") (part "PINHD-1X1"))
    )
    (comp (ref "SW1")
      (value "SWITCH_SPST_4_PINRECT")
      (footprint "eagle-import:TACTILE_SWITCH_SMD_4.6X2.8MM")
      (libsource (lib "eagle-import") (part "SWITCH_SPST_4_PINRECT"))
    )
    (comp (ref "SWCLK")
      (value "PINHD-1X1")
      (footprint "eagle-import:1X01")
      (libsource (lib "eagle-import") (part "PINHD-1X1"))
    )
    (comp (ref "SWDIO")
      (value "PINHD-1X1")
      (footprint "eagle-import:1X01")
      (libsource (lib "eagle-import") (part "PINHD-1X1"))
    )
    (comp (ref "U1")
      (value "MCP111T-240E/TT")
      (footprint "eagle-import:SOT95P237X112-3N")
      (fields (field (name "MPN") "MCP111T-270E/TT") (field (name "MPN_1") "MCP111T-240E/TT"))
      (libsource (lib "eagle-import") (part "MCP111T-270E/TT"))
    )
    (comp (ref "U2")
      (value "SPX3819-3.3")
      (footprint "eagle-import:SOT23-5")
      (libsource (lib "eagle-import") (part "VREG_SOT23-5"))
    )
    (comp (ref "U5")
      (value "ATSAMD21G18_QFN")
      (footprint "eagle-import:TQFN48_7MM")
      (libsource (lib "eagle-import") (part "ATSAMD21J_QFN"))
    )
    (comp (ref "U7")
      (value "LT1634-1,25BMCMS8")
      (footprint "eagle-import:MSOP8")
      (libsource (lib "eagle-import") (part "LT1634BMCMS8-1,25"))
    )
    (comp (ref "VBUS")
      (value "PINHD-1X1")
      (footprint "eagle-import:1X01")
      (libsource (lib "eagle-import") (part "PINHD-1X1"))
    )
    (comp (ref "X1")
      (value "32.768")
      (footprint "eagle-import:XTAL3215")
      (libsource (lib "eagle-import") (part "XTAL-3.2X1.5"))
    )
  )
  (nets
    (net (code "1") (name "+3V3") (class "Default")
      (node (ref "3V3") (pin "1") (pinfunction "1_1") (pintype "passive"))
      (node (ref "C10") (pin "1") (pinfunction "1_1") (pintype "passive"))
      (node (ref "C19") (pin "1") (pinfunction "1_1") (pintype "passive"))
      (node (ref "C5") (pin "1") (pinfunction "1_1") (pintype "passive"))
      (node (ref "C7") (pin "1") (pinfunction "1_1") (pintype "passive"))
      (node (ref "C8") (pin "1") (pinfunction "1_1") (pintype "passive"))
      (node (ref "LED1") (pin "1") (pinfunction "VDD_1") (pintype "power_in"))
      (node (ref "Q1") (pin "2") (pinfunction "S_2") (pintype "passive"))
      (node (ref "Q2") (pin "2") (pinfunction "S_2") (pintype "passive"))
      (node (ref "Q3") (pin "2") (pinfunction "S_2") (pintype "passive"))
      (node (ref "R1") (pin "1") (pinfunction "1_1") (pintype "passive"))
      (node (ref "R12") (pin "2") (pinfunction "2_2") (pintype "passive"))
      (node (ref "R13") (pin "2") (pinfunction "2_2") (pintype "passive"))
      (node (ref "R4") (pin "2") (pinfunction "2_2") (pintype "passive"))
      (node (ref "R5") (pin "1") (pinfunction "1_1") (pintype "passive"))
      (node (ref "R8") (pin "1") (pinfunction "1_1") (pintype "passive"))
      (node (ref "U1") (pin "3") (pinfunction "VDD_3") (pintype "power_in"))
      (node (ref "U2") (pin "5") (pinfunction "OUT_5") (pintype "power_in"))
      (node (ref "U5") (pin "17") (pinfunction "VDDIO_17") (pintype "power_in"))
      (node (ref "U5") (pin "36") (pinfunction "VDDIO_36") (pintype "power_in"))
      (node (ref "U5") (pin "44") (pinfunction "VDDIN_44") (pintype "power_in"))
      (node (ref "U5") (pin "6") (pinfunction "VDDA_6") (pintype "power_in"))
      (node (ref "U6") (pin "6_V_BCKP") (pinfunction "6_V_BCKP_6_V_BCKP") (pintype "bidirectional"))
    )
    (net (code "2") (name "3V3SW") (class "Default")
      (node (ref "3V3SW") (pin "1") (pinfunction "1_1") (pintype "passive"))
      (node (ref "C3") (pin "1") (pinfunction "1_1") (pintype "passive"))
      (node (ref "C9") (pin "1") (pinfunction "1_1") (pintype "passive"))
      (node (ref "Q1") (pin "3") (pinfunction "D_3") (pintype "passive"))
      (node (ref "U4") (pin "1") (pinfunction "VDD_1") (pintype "power_in"))
      (node (ref "U4") (pin "4") (pinfunction "VDDIO_4") (pintype "power_in"))
      (node (ref "U6") (pin "7_VCC_IO") (pinfunction "7_VCC_IO_7_VCC_IO") (pintype "power_in"))
      (node (ref "U6") (pin "8_VCC") (pinfunction "8_VCC_8_VCC") (pintype "power_in"))
    )
    (net (code "3") (name "9_V_RESET_N") (class "Default")
      (node (ref "U6") (pin "9_RESET_N") (pinfunction "9_V_RESET_N_9_RESET_N") (pintype "power_in"))
    )
    (net (code "4") (name "A0") (class "Default")
      (node (ref "R7") (pin "2") (pinfunction "2_2") (pintype "passive"))
      (node (ref "U5") (pin "3") (pinfunction "PA02/EINT2/AIN0/Y0/VOUT_3") (pintype "bidirectional"))
      (node (ref "U7") (pin "6") (pinfunction "VOUT_6") (pintype "passive"))
    )
    (net (code "5") (name "A1") (class "Default")
      (node (ref "R4") (pin "1") (pinfunction "1_1") (pintype "passive"))
      (node (ref "U3") (pin "5") (pinfunction "PGOOD_5") (pintype "output"))
      (node (ref "U5") (pin "7") (pinfunction "PB08/I8/AIN2/SERCOM4.0_7") (pintype "bidirectional"))
    )
    (net (code "6") (name "A2") (class "Default")
      (node (ref "U5") (pin "8") (pinfunction "PB09/I9/AIN3/SERCOM4.1_8") (pintype "bidirectional"))
    )
    (net (code "7") (name "A3") (class "Default")
      (node (ref "J1") (pin "12") (pinfunction "12_12") (pintype "bidirectional"))
      (node (ref "U5") (pin "9") (pinfunction "PA04/EINT4/VREFB/AIN4/SERCOM0.0_9") (pintype "bidirectional"))
    )
    (net (code "8") (name "A4") (class "Default")
      (node (ref "U5") (pin "10") (pinfunction "PA05/EINT5/AIN5/SERCOM0.1_10") (pintype "bidirectional"))
    )
    (net (code "9") (name "A5") (class "Default")
      (node (ref "R14") (pin "1") (pinfunction "1_1") (pintype "passive"))
      (node (ref "R17") (pin "1") (pinfunction "1_1") (pintype "passive"))
      (node (ref "U5") (pin "47") (pinfunction "PB02/I2/AIN10/SERCOM5.0_47") (pintype "bidirectional"))
    )
    (net (code "10") (name "AREF") (class "Default")
      (node (ref "C14") (pin "1") (pinfunction "1_1") (pintype "passive"))
      (node (ref "U5") (pin "4") (pinfunction "PA03/EINT3/VREFA/AIN1_4") (pintype "bidirectional"))
    )
    (net (code "11") (name "D+") (class "Default")
      (node (ref "CON1") (pin "D+") (pinfunction "D+_D+") (pintype "bidirectional"))
      (node (ref "U5") (pin "34") (pinfunction "PA25/I13/SERCOM3+5.3/D+_34") (pintype "bidirectional"))
    )
    (net (code "12") (name "D-") (class "Default")
      (node (ref "CON1") (pin "D-") (pinfunction "D-_D-") (pintype "bidirectional"))
      (node (ref "U5") (pin "33") (pinfunction "PA24/I12/SERCOM3+5.2/D-_33") (pintype "bidirectional"))
    )
    (net (code "13") (name "D0") (class "Default")
      (node (ref "U5") (pin "16") (pinfunction "PA11/I11/AIN19/SERCOM0+2.3/I2SF0_16") (pintype "bidirectional"))
      (node (ref "U6") (pin "2_TXD") (pinfunction "2_TXD_2_TXD") (pintype "bidirectional"))
    )
    (net (code "14") (name "D1") (class "Default")
      (node (ref "U5") (pin "15") (pinfunction "PA10/I10/AIN18/SERCOM0+2.2/I2SCK_15") (pintype "bidirectional"))
      (node (ref "U6") (pin "3_RXD") (pinfunction "3_RXD_3_RXD") (pintype "bidirectional"))
    )
    (net (code "15") (name "D2") (class "Default")
      (node (ref "Q3") (pin "1") (pinfunction "G_1") (pintype "passive"))
      (node (ref "R13") (pin "1") (pinfunction "1_1") (pintype "passive"))
      (node (ref "U5") (pin "23") (pinfunction "PA14/I14/SERCOM2+4.2_23") (pintype "bidirectional"))
    )
    (net (code "16") (name "D3") (class "Default")
      (node (ref "U5") (pin "14") (pinfunction "PA09/I2C/I9/AIN17/SERCOM0+2.1/I2SMC_14") (pintype "bidirectional"))
    )
    (net (code "17") (name "D5") (class "Default")
      (node (ref "R16") (pin "1") (pinfunction "1_1") (pintype "passive"))
      (node (ref "U3") (pin "4") (pinfunction "~{SHDN}_4") (pintype "input"))
      (node (ref "U5") (pin "24") (pinfunction "PA15/I15/SERCOM3+4.3_24") (pintype "bidirectional"))
    )
    (net (code "18") (name "D6") (class "Default")
      (node (ref "J1") (pin "5") (pinfunction "5_5") (pintype "bidirectional"))
      (node (ref "U5") (pin "29") (pinfunction "PA20/I4/SERCOM3+5.2/I2SSC_29") (pintype "bidirectional"))
    )
    (net (code "19") (name "D7") (class "Default")
      (node (ref "Q2") (pin "1") (pinfunction "G_1") (pintype "passive"))
      (node (ref "R12") (pin "1") (pinfunction "1_1") (pintype "passive"))
      (node (ref "U5") (pin "30") (pinfunction "PA21/I5/SERCOM3+5.3/I2SFS0_30") (pintype "bidirectional"))
    )
    (net (code "20") (name "D8") (class "Default")
      (node (ref "U5") (pin "11") (pinfunction "PA06/EINT6/AIN6/SERCOM0.2_11") (pintype "bidirectional"))
    )
    (net (code "21") (name "D9") (class "Default")
      (node (ref "R3") (pin "1") (pinfunction "1_1") (pintype "passive"))
      (node (ref "R6") (pin "2") (pinfunction "2_2") (pintype "passive"))
      (node (ref "U5") (pin "12") (pinfunction "PA07/I7/AIN7/SERCOM0.3/I2SD0_12") (pintype "bidirectional"))
    )
    (net (code "22") (name "D10") (class "Default")
      (node (ref "J1") (pin "6") (pinfunction "6_6") (pintype "bidirectional"))
      (node (ref "U5") (pin "27") (pinfunction "PA18/I2/SERCOM1+3.2_27") (pintype "bidirectional"))
    )
    (net (code "23") (name "D11") (class "Default")
      (node (ref "Q1") (pin "1") (pinfunction "G_1") (pintype "passive"))
      (node (ref "R1") (pin "2") (pinfunction "2_2") (pintype "passive"))
      (node (ref "U5") (pin "25") (pinfunction "PA16/I2C/I0/SERCOM1+3.0_25") (pintype "bidirectional"))
    )
    (net (code "24") (name "D12") (class "Default")
      (node (ref "J1") (pin "7") (pinfunction "7_7") (pintype "bidirectional"))
      (node (ref "U5") (pin "28") (pinfunction "PA19/I3/SERCOM1+3.3/I2SD0_28") (pintype "bidirectional"))
    )
    (net (code "25") (name "D13") (class "Default")
      (node (ref "LED1") (pin "4") (pinfunction "DIN_4") (pintype "input"))
      (node (ref "R10") (pin "1") (pinfunction "1_1") (pintype "passive"))
      (node (ref "U5") (pin "26") (pinfunction "PA17/I2C/I1/SERCOM1+3.1_26") (pintype "bidirectional"))
    )
    (net (code "26") (name "EXT_PWR") (class "Default")
      (node (ref "J1") (pin "1") (pinfunction "1_1") (pintype "bidirectional"))
      (node (ref "J1") (pin "2") (pinfunction "2_2") (pintype "bidirectional"))
      (node (ref "Q4") (pin "3") (pinfunction "D_3") (pintype "passive"))
    )
    (net (code "27") (name "GND") (class "Default")
      (node (ref "C1") (pin "2") (pinfunction "2_2") (pintype "passive"))
      (node (ref "C10") (pin "2") (pinfunction "2_2") (pintype "passive"))
      (node (ref "C12") (pin "-") (pinfunction "-_-") (pintype "passive"))
      (node (ref "C13") (pin "2") (pinfunction "2_2") (pintype "passive"))
      (node (ref "C14") (pin "2") (pinfunction "2_2") (pintype "passive"))
      (node (ref "C16") (pin "2") (pinfunction "2_2") (pintype "passive"))
      (node (ref "C17") (pin "2") (pinfunction "2_2") (pintype "passive"))
      (node (ref "C18") (pin "2") (pinfunction "2_2") (pintype "passive"))
      (node (ref "C19") (pin "2") (pinfunction "2_2") (pintype "passive"))
      (node (ref "C2") (pin "2") (pinfunction "2_2") (pintype "passive"))
      (node (ref "C3") (pin "2") (pinfunction "2_2") (pintype "passive"))
      (node (ref "C4") (pin "2") (pinfunction "2_2") (pintype "passive"))
      (node (ref "C5") (pin "2") (pinfunction "2_2") (pintype "passive"))
      (node (ref "C6") (pin "2") (pinfunction "2_2") (pintype "passive"))
      (node (ref "C7") (pin "2") (pinfunction "2_2") (pintype "passive"))
      (node (ref "C8") (pin "2") (pinfunction "2_2") (pintype "passive"))
      (node (ref "C9") (pin "2") (pinfunction "2_2") (pintype "passive"))
      (node (ref "CON1") (pin "BASE@1") (pinfunction "GND_BASE@1") (pintype "power_in"))
      (node (ref "CON1") (pin "BASE@2") (pinfunction "GND_BASE@2") (pintype "power_in"))
      (node (ref "CON1") (pin "GND") (pinfunction "GND_GND") (pintype "power_in"))
      (node (ref "CON1") (pin "SPRT@1") (pinfunction "GND_SPRT@1") (pintype "power_in"))
      (node (ref "CON1") (pin "SPRT@2") (pinfunction "GND_SPRT@2") (pintype "power_in"))
      (node (ref "CON1") (pin "SPRT@3") (pinfunction "GND_SPRT@3") (pintype "power_in"))
      (node (ref "CON1") (pin "SPRT@4") (pinfunction "GND_SPRT@4") (pintype "power_in"))
      (node (ref "D2") (pin "A") (pinfunction "A_A") (pintype "passive"))
      (node (ref "D3") (pin "A") (pinfunction "A_A") (pintype "passive"))
      (node (ref "GND") (pin "1") (pinfunction "1_1") (pintype "passive"))
      (node (ref "GND2") (pin "1") (pinfunction "1_1") (pintype "passive"))
      (node (ref "GND3") (pin "1") (pinfunction "1_1") (pintype "passive"))
      (node (ref "GNSS") (pin "G@1") (pinfunction "2_G@1") (pintype "passive"))
      (node (ref "GNSS") (pin "G@2") (pinfunction "2_G@2") (pintype "passive"))
      (node (ref "GNSS") (pin "G@3") (pinfunction "2_G@3") (pintype "passive"))
      (node (ref "GNSS") (pin "G@4") (pinfunction "2_G@4") (pintype "passive"))
      (node (ref "J1") (pin "13") (pinfunction "13_13") (pintype "bidirectional"))
      (node (ref "J1") (pin "14") (pinfunction "14_14") (pintype "bidirectional"))
      (node (ref "J1") (pin "15") (pinfunction "15_15") (pintype "bidirectional"))
      (node (ref "J1") (pin "18") (pinfunction "18_18") (pintype "bidirectional"))
      (node (ref "J1") (pin "3") (pinfunction "3_3") (pintype "bidirectional"))
      (node (ref "J1") (pin "4") (pinfunction "4_4") (pintype "bidirectional"))
      (node (ref "J1") (pin "8") (pinfunction "8_8") (pintype "bidirectional"))
      (node (ref "JP1") (pin "1") (pinfunction "1_1") (pintype "passive"))
      (node (ref "LED1") (pin "3") (pinfunction "VSS_3") (pintype "power_in"))
      (node (ref "LED2") (pin "C") (pinfunction "C_C") (pintype "passive"))
      (node (ref "Q5") (pin "E") (pinfunction "E_E") (pintype "passive"))
      (node (ref "R11") (pin "1") (pinfunction "1_1") (pintype "passive"))
      (node (ref "R16") (pin "2") (pinfunction "2_2") (pintype "passive"))
      (node (ref "R17") (pin "2") (pinfunction "2_2") (pintype "passive"))
      (node (ref "R2") (pin "1") (pinfunction "1_1") (pintype "passive"))
      (node (ref "R6") (pin "1") (pinfunction "1_1") (pintype "passive"))
      (node (ref "RELAY1") (pin "12") (pinfunction "COIL1-_12") (pintype "input"))
      (node (ref "RELAY1") (pin "7") (pinfunction "COIL2-_7") (pintype "input"))
      (node (ref "S1") (pin "P1") (pinfunction "P$1_P1") (pintype "bidirectional"))
      (node (ref "S2") (pin "P1") (pinfunction "P$1_P1") (pintype "bidirectional"))
      (node (ref "SOLAR1-") (pin "1") (pinfunction "1_1") (pintype "passive"))
      (node (ref "SOLAR2-") (pin "1") (pinfunction "1_1") (pintype "passive"))
      (node (ref "SW1") (pin "3") (pinfunction "3_3") (pintype "passive"))
      (node (ref "SW1") (pin "4") (pinfunction "4_4") (pintype "passive"))
      (node (ref "U1") (pin "2") (pinfunction "VSS_2") (pintype "power_in"))
      (node (ref "U2") (pin "2") (pinfunction "GND_2") (pintype "power_in"))
      (node (ref "U3") (pin "11") (pinfunction "GND_2_11") (pintype "passive"))
      (node (ref "U3") (pin "8") (pinfunction "GND_8") (pintype "passive"))
      (node (ref "U4") (pin "3") (pinfunction "GND_3") (pintype "power_in"))
      (node (ref "U5") (pin "18") (pinfunction "GND_18") (pintype "power_in"))
      (node (ref "U5") (pin "35") (pinfunction "GND_35") (pintype "power_in"))
      (node (ref "U5") (pin "42") (pinfunction "GND_42") (pintype "power_in"))
      (node (ref "U5") (pin "5") (pinfunction "GNDA_5") (pintype "power_in"))
      (node (ref "U5") (pin "THERMAL") (pinfunction "GND_THERMAL") (pintype "power_in"))
      (node (ref "U6") (pin "10_GND") (pinfunction "10_GND_10_GND") (pintype "power_in"))
      (node (ref "U6") (pin "12_GND") (pinfunction "12_GND_12_GND") (pintype "power_in"))
      (node (ref "U6") (pin "1_GND") (pinfunction "1_GND_1_GND") (pintype "power_in"))
      (node (ref "U7") (pin "4") (pinfunction "GND_4") (pintype "passive"))
    )
    (net (code "28") (name "GNDA") (class "Default")
      (node (ref "CON4") (pin "1") (pinfunction "GND_1") (pintype "passive"))
      (node (ref "CON4") (pin "2") (pinfunction "GND_2") (pintype "passive"))
      (node (ref "IRIDIUM") (pin "G@1") (pinfunction "2_G@1") (pintype "passive"))
      (node (ref "IRIDIUM") (pin "G@2") (pinfunction "2_G@2") (pintype "passive"))
      (node (ref "IRIDIUM") (pin "G@3") (pinfunction "2_G@3") (pintype "passive"))
      (node (ref "IRIDIUM") (pin "G@4") (pinfunction "2_G@4") (pintype "passive"))
    )
    (net (code "29") (name "GPS_ANT") (class "Default")
      (node (ref "GNSS") (pin "1") (pinfunction "1_1") (pintype "passive"))
      (node (ref "L1") (pin "2") (pinfunction "P$2_2") (pintype "passive"))
      (node (ref "U6") (pin "11_RF_IN") (pinfunction "11_RF_IN_11_RF_IN") (pintype "bidirectional"))
    )
    (net (code "30") (name "LTC3225_VOUT") (class "Default")
      (node (ref "C11") (pin "+") (pinfunction "+_+") (pintype "passive"))
      (node (ref "C16") (pin "1") (pinfunction "1_1") (pintype "passive"))
      (node (ref "Q4") (pin "2") (pinfunction "S_2") (pintype "passive"))
      (node (ref "R15") (pin "1") (pinfunction "1_1") (pintype "passive"))
      (node (ref "U3") (pin "10") (pinfunction "COUT_10") (pintype "output"))
    )
    (net (code "31") (name "MISO") (class "Default")
      (node (ref "MISO") (pin "1") (pinfunction "1_1") (pintype "passive"))
      (node (ref "U5") (pin "21") (pinfunction "PA12/I12/I2C/SERCOM2+4.0_21") (pintype "bidirectional"))
    )
    (net (code "32") (name "MOSI") (class "Default")
      (node (ref "MOSI") (pin "1") (pinfunction "1_1") (pintype "passive"))
      (node (ref "U5") (pin "19") (pinfunction "PB10/I10/SERCOM4.2/I2SMC_19") (pintype "bidirectional"))
    )
    (net (code "33") (name "Net-(BAT--Pad1)") (class "Default")
      (node (ref "BAT-") (pin "1") (pinfunction "1_1") (pintype "passive"))
      (node (ref "BAT3") (pin "GND@1") (pinfunction "-_GND@1") (pintype "power_in"))
      (node (ref "BAT3") (pin "GND@2") (pinfunction "-_GND@2") (pintype "power_in"))
    )
    (net (code "34") (name "Net-(BAT1---PadGND@1)") (class "Default")
      (node (ref "BAT1") (pin "GND@1") (pinfunction "-_GND@1") (pintype "power_in"))
      (node (ref "BAT1") (pin "GND@2") (pinfunction "-_GND@2") (pintype "power_in"))
      (node (ref "BAT2") (pin "PWR@1") (pinfunction "+_PWR@1") (pintype "power_in"))
      (node (ref "BAT2") (pin "PWR@2") (pinfunction "+_PWR@2") (pintype "power_in"))
    )
    (net (code "35") (name "Net-(BAT2---PadGND@1)") (class "Default")
      (node (ref "BAT2") (pin "GND@1") (pinfunction "-_GND@1") (pintype "power_in"))
      (node (ref "BAT2") (pin "GND@2") (pinfunction "-_GND@2") (pintype "power_in"))
      (node (ref "BAT3") (pin "PWR@1") (pinfunction "+_PWR@1") (pintype "power_in"))
      (node (ref "BAT3") (pin "PWR@2") (pinfunction "+_PWR@2") (pintype "power_in"))
    )
    (net (code "36") (name "Net-(CON1-PadVBUS)") (class "Default")
      (node (ref "CON1") (pin "VBUS") (pinfunction "VBUS_VBUS") (pintype "power_in"))
      (node (ref "D4") (pin "A") (pinfunction "A_A") (pintype "passive"))
    )
    (net (code "37") (name "Net-(CON4-SIGNAL)") (class "Default")
      (node (ref "CON4") (pin "3") (pinfunction "SIGNAL_3") (pintype "passive"))
      (node (ref "IRIDIUM") (pin "1") (pinfunction "1_1") (pintype "passive"))
    )
    (net (code "38") (name "Net-(D5-PadA)") (class "Default")
      (node (ref "D5") (pin "A") (pinfunction "A_A") (pintype "passive"))
      (node (ref "SOLAR2+") (pin "1") (pinfunction "1_1") (pintype "passive"))
    )
    (net (code "39") (name "Net-(D6-PadA)") (class "Default")
      (node (ref "D6") (pin "A") (pinfunction "A_A") (pintype "passive"))
      (node (ref "SOLAR1+") (pin "1") (pinfunction "1_1") (pintype "passive"))
    )
    (net (code "40") (name "Net-(JP2-Pad1)") (class "Default")
      (node (ref "JP2") (pin "1") (pinfunction "1_1") (pintype "passive"))
      (node (ref "R11") (pin "2") (pinfunction "2_2") (pintype "passive"))
    )
    (net (code "41") (name "Net-(JP2-Pad3)") (class "Default")
      (node (ref "JP2") (pin "3") (pinfunction "3_3") (pintype "passive"))
      (node (ref "R2") (pin "2") (pinfunction "2_2") (pintype "passive"))
    )
    (net (code "42") (name "Net-(L1-P$1)") (class "Default")
      (node (ref "C18") (pin "1") (pinfunction "1_1") (pintype "passive"))
      (node (ref "L1") (pin "1") (pinfunction "P$1_1") (pintype "passive"))
      (node (ref "R9") (pin "1") (pinfunction "1_1") (pintype "passive"))
    )
    (net (code "43") (name "Net-(LED2-PadA)") (class "Default")
      (node (ref "LED2") (pin "A") (pinfunction "A_A") (pintype "passive"))
      (node (ref "R10") (pin "2") (pinfunction "2_2") (pintype "passive"))
    )
    (net (code "44") (name "Net-(Q4-G)") (class "Default")
      (node (ref "Q4") (pin "1") (pinfunction "G_1") (pintype "passive"))
      (node (ref "Q5") (pin "C") (pinfunction "C_C") (pintype "passive"))
      (node (ref "R15") (pin "2") (pinfunction "2_2") (pintype "passive"))
    )
    (net (code "45") (name "Net-(Q5-PadB)") (class "Default")
      (node (ref "Q5") (pin "B") (pinfunction "B_B") (pintype "passive"))
      (node (ref "R14") (pin "2") (pinfunction "2_2") (pintype "passive"))
    )
    (net (code "46") (name "Net-(RELAY1-COM(1))") (class "Default")
      (node (ref "COM1") (pin "1") (pinfunction "1_1") (pintype "passive"))
      (node (ref "RELAY1") (pin "4") (pinfunction "COM(1)_4") (pintype "input"))
    )
    (net (code "47") (name "Net-(RELAY1-COM(2))") (class "Default")
      (node (ref "COM2") (pin "1") (pinfunction "1_1") (pintype "passive"))
      (node (ref "RELAY1") (pin "9") (pinfunction "COM(2)_9") (pintype "input"))
    )
    (net (code "48") (name "Net-(RELAY1-NC(1))") (class "Default")
      (node (ref "NC1") (pin "1") (pinfunction "1_1") (pintype "passive"))
      (node (ref "RELAY1") (pin "3") (pinfunction "NC(1)_3") (pintype "input"))
    )
    (net (code "49") (name "Net-(RELAY1-NC(2))") (class "Default")
      (node (ref "NC2") (pin "1") (pinfunction "1_1") (pintype "passive"))
      (node (ref "RELAY1") (pin "10") (pinfunction "NC(2)_10") (pintype "input"))
    )
    (net (code "50") (name "Net-(RELAY1-NO(1))") (class "Default")
      (node (ref "NO1") (pin "1") (pinfunction "1_1") (pintype "passive"))
      (node (ref "RELAY1") (pin "5") (pinfunction "NO(1)_5") (pintype "input"))
    )
    (net (code "51") (name "Net-(RELAY1-NO(2))") (class "Default")
      (node (ref "NO2") (pin "1") (pinfunction "1_1") (pintype "passive"))
      (node (ref "RELAY1") (pin "8") (pinfunction "NO(2)_8") (pintype "input"))
    )
    (net (code "52") (name "Net-(U3-C+)") (class "Default")
      (node (ref "C15") (pin "1") (pinfunction "1_1") (pintype "passive"))
      (node (ref "U3") (pin "1") (pinfunction "C+_1") (pintype "passive"))
    )
    (net (code "53") (name "Net-(U3-C-)") (class "Default")
      (node (ref "C15") (pin "2") (pinfunction "2_2") (pintype "passive"))
      (node (ref "U3") (pin "2") (pinfunction "C-_2") (pintype "passive"))
    )
    (net (code "54") (name "Net-(U3-CX)") (class "Default")
      (node (ref "C11") (pin "-") (pinfunction "-_-") (pintype "passive"))
      (node (ref "C12") (pin "+") (pinfunction "+_+") (pintype "passive"))
      (node (ref "U3") (pin "3") (pinfunction "CX_3") (pintype "passive"))
    )
    (net (code "55") (name "Net-(U3-PROG)") (class "Default")
      (node (ref "JP2") (pin "2") (pinfunction "2_2") (pintype "passive"))
      (node (ref "U3") (pin "7") (pinfunction "PROG_7") (pintype "input"))
    )
    (net (code "56") (name "Net-(U3-VSEL)") (class "Default")
      (node (ref "JP1") (pin "2") (pinfunction "2_2") (pintype "passive"))
      (node (ref "U3") (pin "6") (pinfunction "VSEL_6") (pintype "input"))
    )
    (net (code "57") (name "Net-(U4-CAP)") (class "Default")
      (node (ref "C13") (pin "1") (pinfunction "1_1") (pintype "passive"))
      (node (ref "U4") (pin "2") (pinfunction "CAP_2") (pintype "power_in"))
    )
    (net (code "58") (name "Net-(U5-PA00{slash}EINT0{slash}SERCOM1.0)") (class "Default")
      (node (ref "C2") (pin "1") (pinfunction "1_1") (pintype "passive"))
      (node (ref "U5") (pin "1") (pinfunction "PA00/EINT0/SERCOM1.0_1") (pintype "bidirectional"))
      (node (ref "X1") (pin "P$1") (pinfunction "P$1_P$1") (pintype "bidirectional"))
    )
    (net (code "59") (name "Net-(U5-PA01{slash}EINT1{slash}SERCOM1.1)") (class "Default")
      (node (ref "C4") (pin "1") (pinfunction "1_1") (pintype "passive"))
      (node (ref "U5") (pin "2") (pinfunction "PA01/EINT1/SERCOM1.1_2") (pintype "bidirectional"))
      (node (ref "X1") (pin "P$2") (pinfunction "P$2_P$2") (pintype "bidirectional"))
    )
    (net (code "60") (name "Net-(U5-VDDCORE)") (class "Default")
      (node (ref "C1") (pin "1") (pinfunction "1_1") (pintype "passive"))
      (node (ref "U5") (pin "43") (pinfunction "VDDCORE_43") (pintype "power_in"))
    )
    (net (code "61") (name "RESET_RELAY") (class "Default")
      (node (ref "D3") (pin "C") (pinfunction "C_C") (pintype "passive"))
      (node (ref "Q3") (pin "3") (pinfunction "D_3") (pintype "passive"))
      (node (ref "RELAY1") (pin "6") (pinfunction "COIL2+_6") (pintype "input"))
    )
    (net (code "62") (name "SCK") (class "Default")
      (node (ref "SCK") (pin "1") (pinfunction "1_1") (pintype "passive"))
      (node (ref "U5") (pin "20") (pinfunction "PB11/I11/SERCOM4.3/I2SCL_20") (pintype "bidirectional"))
    )
    (net (code "63") (name "SCL") (class "Default")
      (node (ref "R8") (pin "2") (pinfunction "2_2") (pintype "passive"))
      (node (ref "SCL") (pin "1") (pinfunction "1_1") (pintype "passive"))
      (node (ref "U4") (pin "8") (pinfunction "SCL_8") (pintype "bidirectional"))
      (node (ref "U5") (pin "32") (pinfunction "PA23/I2C/I7/SERCOM3+5.1/SOF_32") (pintype "bidirectional"))
    )
    (net (code "64") (name "SDA") (class "Default")
      (node (ref "R5") (pin "2") (pinfunction "2_2") (pintype "passive"))
      (node (ref "SDA") (pin "1") (pinfunction "1_1") (pintype "passive"))
      (node (ref "U4") (pin "7") (pinfunction "SDA_7") (pintype "bidirectional"))
      (node (ref "U5") (pin "31") (pinfunction "PA22/I2C/I6/SERCOM3+5.0_31") (pintype "bidirectional"))
    )
    (net (code "65") (name "SD_CS") (class "Default")
      (node (ref "CS") (pin "1") (pinfunction "1_1") (pintype "passive"))
      (node (ref "U5") (pin "13") (pinfunction "PA08/I2C/AIN16/SERCOM0+2.0/I2SD1_13") (pintype "bidirectional"))
    )
    (net (code "66") (name "SET_RELAY") (class "Default")
      (node (ref "D2") (pin "C") (pinfunction "C_C") (pintype "passive"))
      (node (ref "Q2") (pin "3") (pinfunction "D_3") (pintype "passive"))
      (node (ref "RELAY1") (pin "1") (pinfunction "COIL1+_1") (pintype "input"))
    )
    (net (code "67") (name "SWCLK") (class "Default")
      (node (ref "SWCLK") (pin "1") (pinfunction "1_1") (pintype "passive"))
      (node (ref "U5") (pin "45") (pinfunction "PA30/I10/SECOM1.2/SWCLK_45") (pintype "bidirectional"))
    )
    (net (code "68") (name "SWDIO") (class "Default")
      (node (ref "SWDIO") (pin "1") (pinfunction "1_1") (pintype "passive"))
      (node (ref "U5") (pin "46") (pinfunction "PA31/I11/SECOM1.3/SWDIO_46") (pintype "bidirectional"))
    )
    (net (code "69") (name "VBAT") (class "Default")
      (node (ref "BAT1") (pin "PWR@1") (pinfunction "+_PWR@1") (pintype "power_in"))
      (node (ref "BAT1") (pin "PWR@2") (pinfunction "+_PWR@2") (pintype "power_in"))
      (node (ref "D1") (pin "A") (pinfunction "A_A") (pintype "passive"))
    )
    (net (code "70") (name "VBUS") (class "Default")
      (node (ref "C17") (pin "1") (pinfunction "1_1") (pintype "passive"))
      (node (ref "C6") (pin "1") (pinfunction "1_1") (pintype "passive"))
      (node (ref "D1") (pin "C") (pinfunction "C_C") (pintype "passive"))
      (node (ref "D4") (pin "C") (pinfunction "C_C") (pintype "passive"))
      (node (ref "D5") (pin "C") (pinfunction "C_C") (pintype "passive"))
      (node (ref "D6") (pin "C") (pinfunction "C_C") (pintype "passive"))
      (node (ref "JP1") (pin "3") (pinfunction "3_3") (pintype "passive"))
      (node (ref "R3") (pin "2") (pinfunction "2_2") (pintype "passive"))
      (node (ref "R7") (pin "1") (pinfunction "1_1") (pintype "passive"))
      (node (ref "U2") (pin "1") (pinfunction "IN_1") (pintype "power_in"))
      (node (ref "U2") (pin "3") (pinfunction "EN_3") (pintype "input"))
      (node (ref "U3") (pin "9") (pinfunction "VIN_9") (pintype "power_in"))
      (node (ref "VBUS") (pin "1") (pinfunction "1_1") (pintype "passive"))
    )
    (net (code "71") (name "VCC_RF") (class "Default")
      (node (ref "R9") (pin "2") (pinfunction "2_2") (pintype "passive"))
      (node (ref "U6") (pin "14_VCC_RF") (pinfunction "14_VCC_RF_14_VCC_RF") (pintype "bidirectional"))
    )
    (net (code "72") (name "unconnected-(CON1-PadID)") (class "Default")
      (node (ref "CON1") (pin "ID") (pinfunction "ID_ID") (pintype "bidirectional"))
    )
    (net (code "73") (name "unconnected-(J1-Pad9)") (class "Default")
      (node (ref "J1") (pin "9") (pinfunction "9_9") (pintype "bidirectional"))
    )
    (net (code "74") (name "unconnected-(J1-Pad10)") (class "Default")
      (node (ref "J1") (pin "10") (pinfunction "10_10") (pintype "bidirectional"))
    )
    (net (code "75") (name "unconnected-(J1-Pad11)") (class "Default")
      (node (ref "J1") (pin "11") (pinfunction "11_11") (pintype "bidirectional"))
    )
    (net (code "76") (name "unconnected-(J1-Pad16)") (class "Default")
      (node (ref "J1") (pin "16") (pinfunction "16_16") (pintype "bidirectional"))
    )
    (net (code "77") (name "unconnected-(J1-Pad17)") (class "Default")
      (node (ref "J1") (pin "17") (pinfunction "17_17") (pintype "bidirectional"))
    )
    (net (code "78") (name "unconnected-(J1-Pad19)") (class "Default")
      (node (ref "J1") (pin "19") (pinfunction "19_19") (pintype "bidirectional"))
    )
    (net (code "79") (name "unconnected-(J1-Pad20)") (class "Default")
      (node (ref "J1") (pin "20") (pinfunction "20_20") (pintype "bidirectional"))
    )
    (net (code "80") (name "unconnected-(LED1-DOUT-Pad2)") (class "Default")
      (node (ref "LED1") (pin "2") (pinfunction "DOUT_2") (pintype "output"))
    )
    (net (code "81") (name "unconnected-(U2-P4-Pad4)") (class "Default")
      (node (ref "U2") (pin "4") (pinfunction "P4_4") (pintype "bidirectional"))
    )
    (net (code "82") (name "unconnected-(U4-INT1-Pad6)") (class "Default")
      (node (ref "U4") (pin "6") (pinfunction "INT1_6") (pintype "output"))
    )
    (net (code "83") (name "unconnected-(U4-INT2-Pad5)") (class "Default")
      (node (ref "U4") (pin "5") (pinfunction "INT2_5") (pintype "output"))
    )
    (net (code "84") (name "unconnected-(U5-PA13{slash}I13{slash}I2C{slash}SERCOM2+4.1-Pad22)") (class "Default")
      (node (ref "U5") (pin "22") (pinfunction "PA13/I13/I2C/SERCOM2+4.1_22") (pintype "bidirectional"))
    )
    (net (code "85") (name "unconnected-(U5-PA27{slash}I15-Pad39)") (class "Default")
      (node (ref "U5") (pin "39") (pinfunction "PA27/I15_39") (pintype "bidirectional"))
    )
    (net (code "86") (name "unconnected-(U5-PA28{slash}I8-Pad41)") (class "Default")
      (node (ref "U5") (pin "41") (pinfunction "PA28/I8_41") (pintype "bidirectional"))
    )
    (net (code "87") (name "unconnected-(U5-PB03{slash}I3{slash}AIN11{slash}SERCOM5.1-Pad48)") (class "Default")
      (node (ref "U5") (pin "48") (pinfunction "PB03/I3/AIN11/SERCOM5.1_48") (pintype "bidirectional"))
    )
    (net (code "88") (name "unconnected-(U5-PB22{slash}I6{slash}SERCOM5.2-Pad37)") (class "Default")
      (node (ref "U5") (pin "37") (pinfunction "PB22/I6/SERCOM5.2_37") (pintype "bidirectional"))
    )
    (net (code "89") (name "unconnected-(U5-PB23{slash}I7{slash}SERCOM5.3-Pad38)") (class "Default")
      (node (ref "U5") (pin "38") (pinfunction "PB23/I7/SERCOM5.3_38") (pintype "bidirectional"))
    )
    (net (code "90") (name "unconnected-(U6-13_LNA_EN{slash}RES-Pad13_LNA_EN)") (class "Default")
      (node (ref "U6") (pin "13_LNA_EN") (pinfunction "13_LNA_EN/RES_13_LNA_EN") (pintype "bidirectional"))
    )
    (net (code "91") (name "unconnected-(U6-15_RES{slash}V_ANT-Pad15_V_ANT{slash}RESERVED)") (class "Default")
      (node (ref "U6") (pin "15_V_ANT/RESERVED") (pinfunction "15_RES/V_ANT_15_V_ANT/RESERVED") (pintype "bidirectional"))
    )
    (net (code "92") (name "unconnected-(U6-Pad4_TIMEPULSE)") (class "Default")
      (node (ref "U6") (pin "4_TIMEPULSE") (pinfunction "4_TIMEPULSE_4_TIMEPULSE") (pintype "bidirectional"))
    )
    (net (code "93") (name "unconnected-(U6-Pad5_EXTINT)") (class "Default")
      (node (ref "U6") (pin "5_EXTINT") (pinfunction "5_EXTINT_5_EXTINT") (pintype "bidirectional"))
    )
    (net (code "94") (name "unconnected-(U6-Pad16_SDA)") (class "Default")
      (node (ref "U6") (pin "16_SDA") (pinfunction "16_SDA_16_SDA") (pintype "bidirectional"))
    )
    (net (code "95") (name "unconnected-(U6-Pad17_SCL)") (class "Default")
      (node (ref "U6") (pin "17_SCL") (pinfunction "17_SCL_17_SCL") (pintype "bidirectional"))
    )
    (net (code "96") (name "unconnected-(U6-Pad18_SAFEBOOT_N)") (class "Default")
      (node (ref "U6") (pin "18_SAFEBOOT_N") (pinfunction "18_SAFEBOOT_N_18_SAFEBOOT_N") (pintype "bidirectional"))
    )
    (net (code "97") (name "~{RESET}") (class "Default")
      (node (ref "RST") (pin "1") (pinfunction "1_1") (pintype "passive"))
      (node (ref "SW1") (pin "1") (pinfunction "1_1") (pintype "passive"))
      (node (ref "SW1") (pin "2") (pinfunction "2_2") (pintype "passive"))
      (node (ref "U1") (pin "1") (pinfunction "VOUT_1") (pintype "output"))
      (node (ref "U5") (pin "40") (pinfunction "/RESET_40") (pintype "bidirectional"))
    )
  )
)
